# rekick2015-fixed-Prototyp.net
KiCad netlist of a schematic drawn in EAGLE
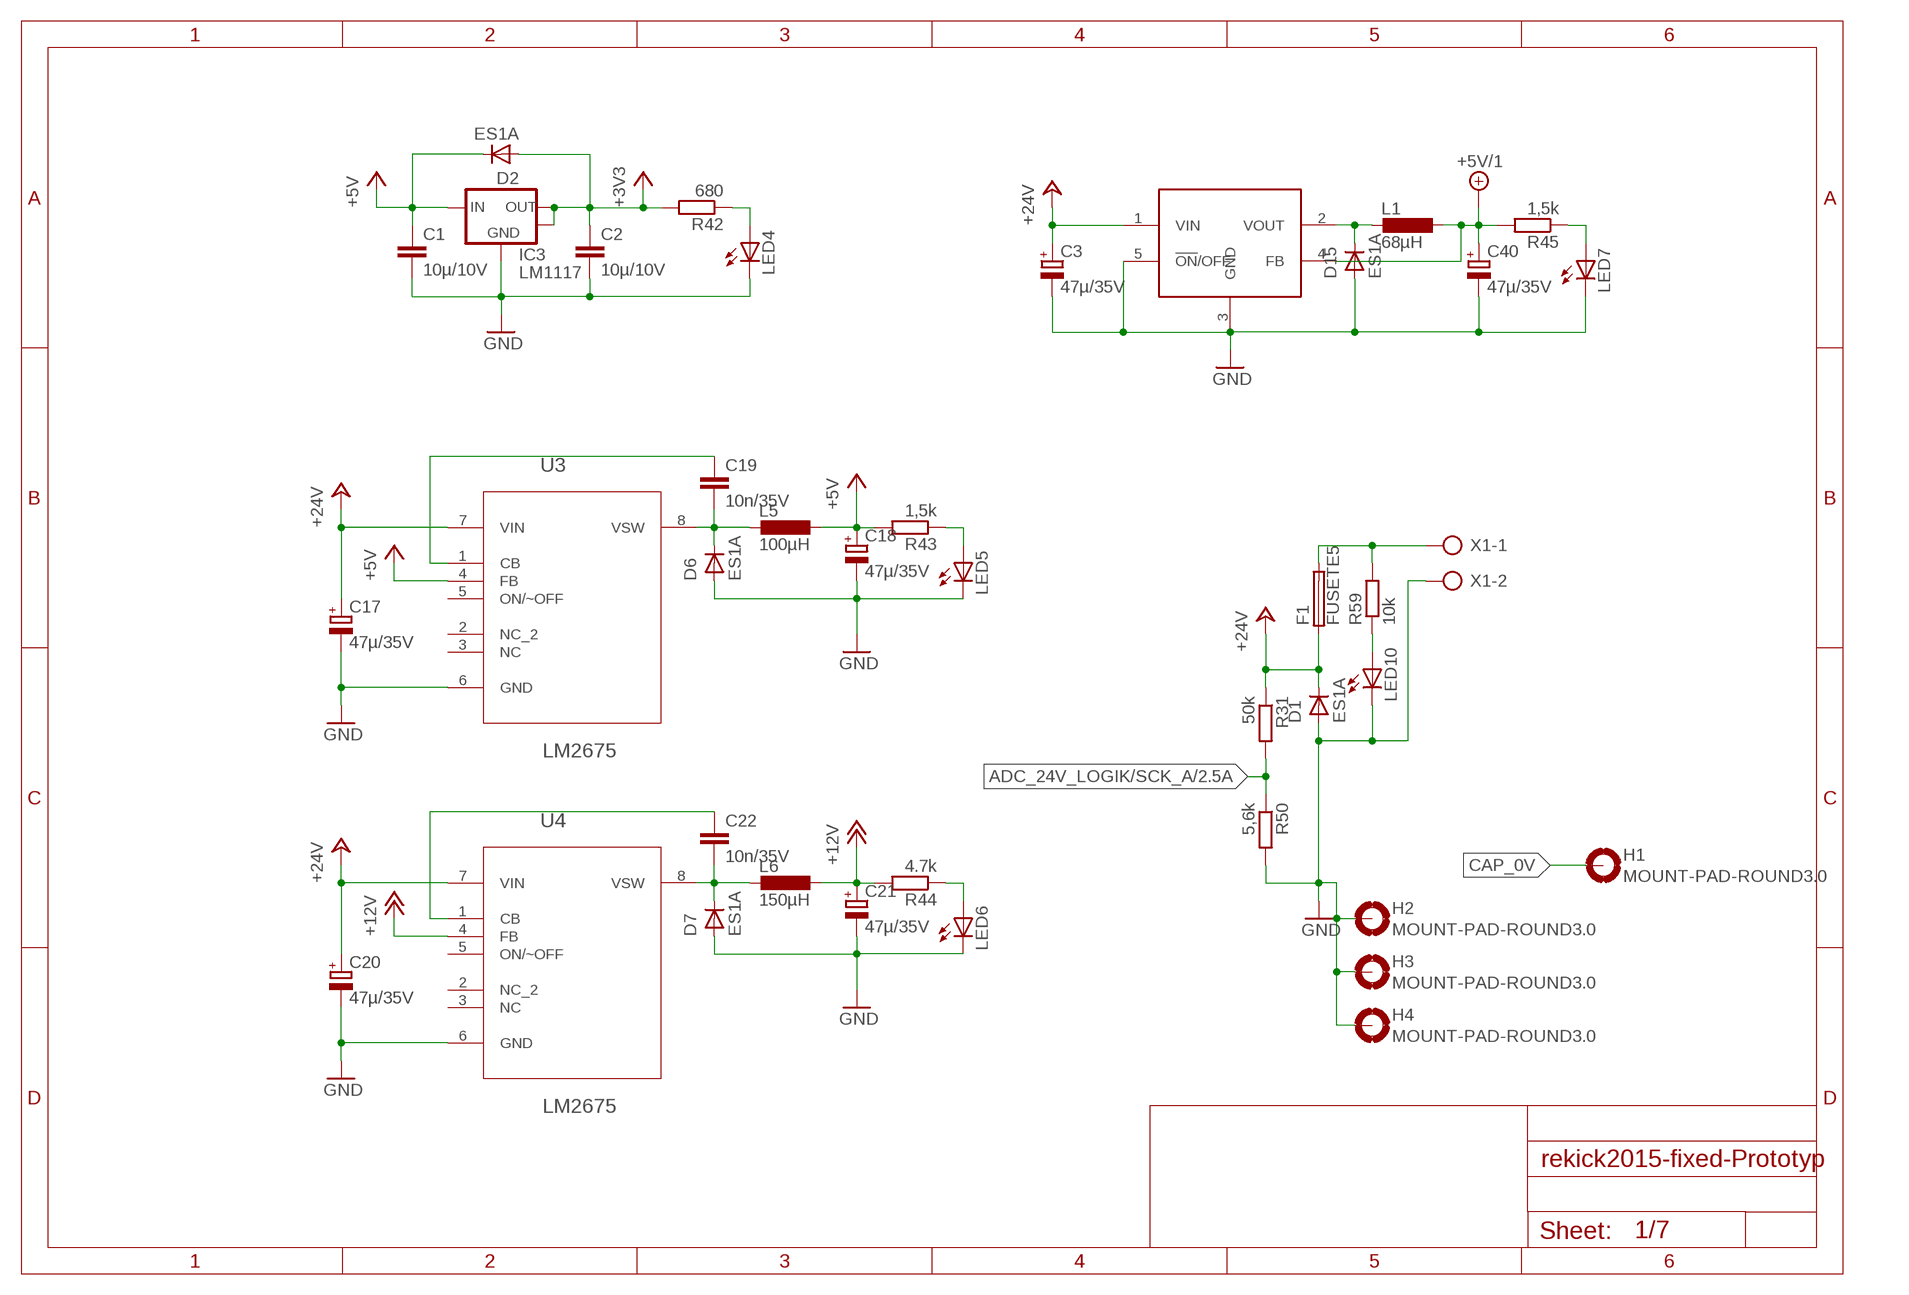
[diagram p0: schematic, sheet 1]
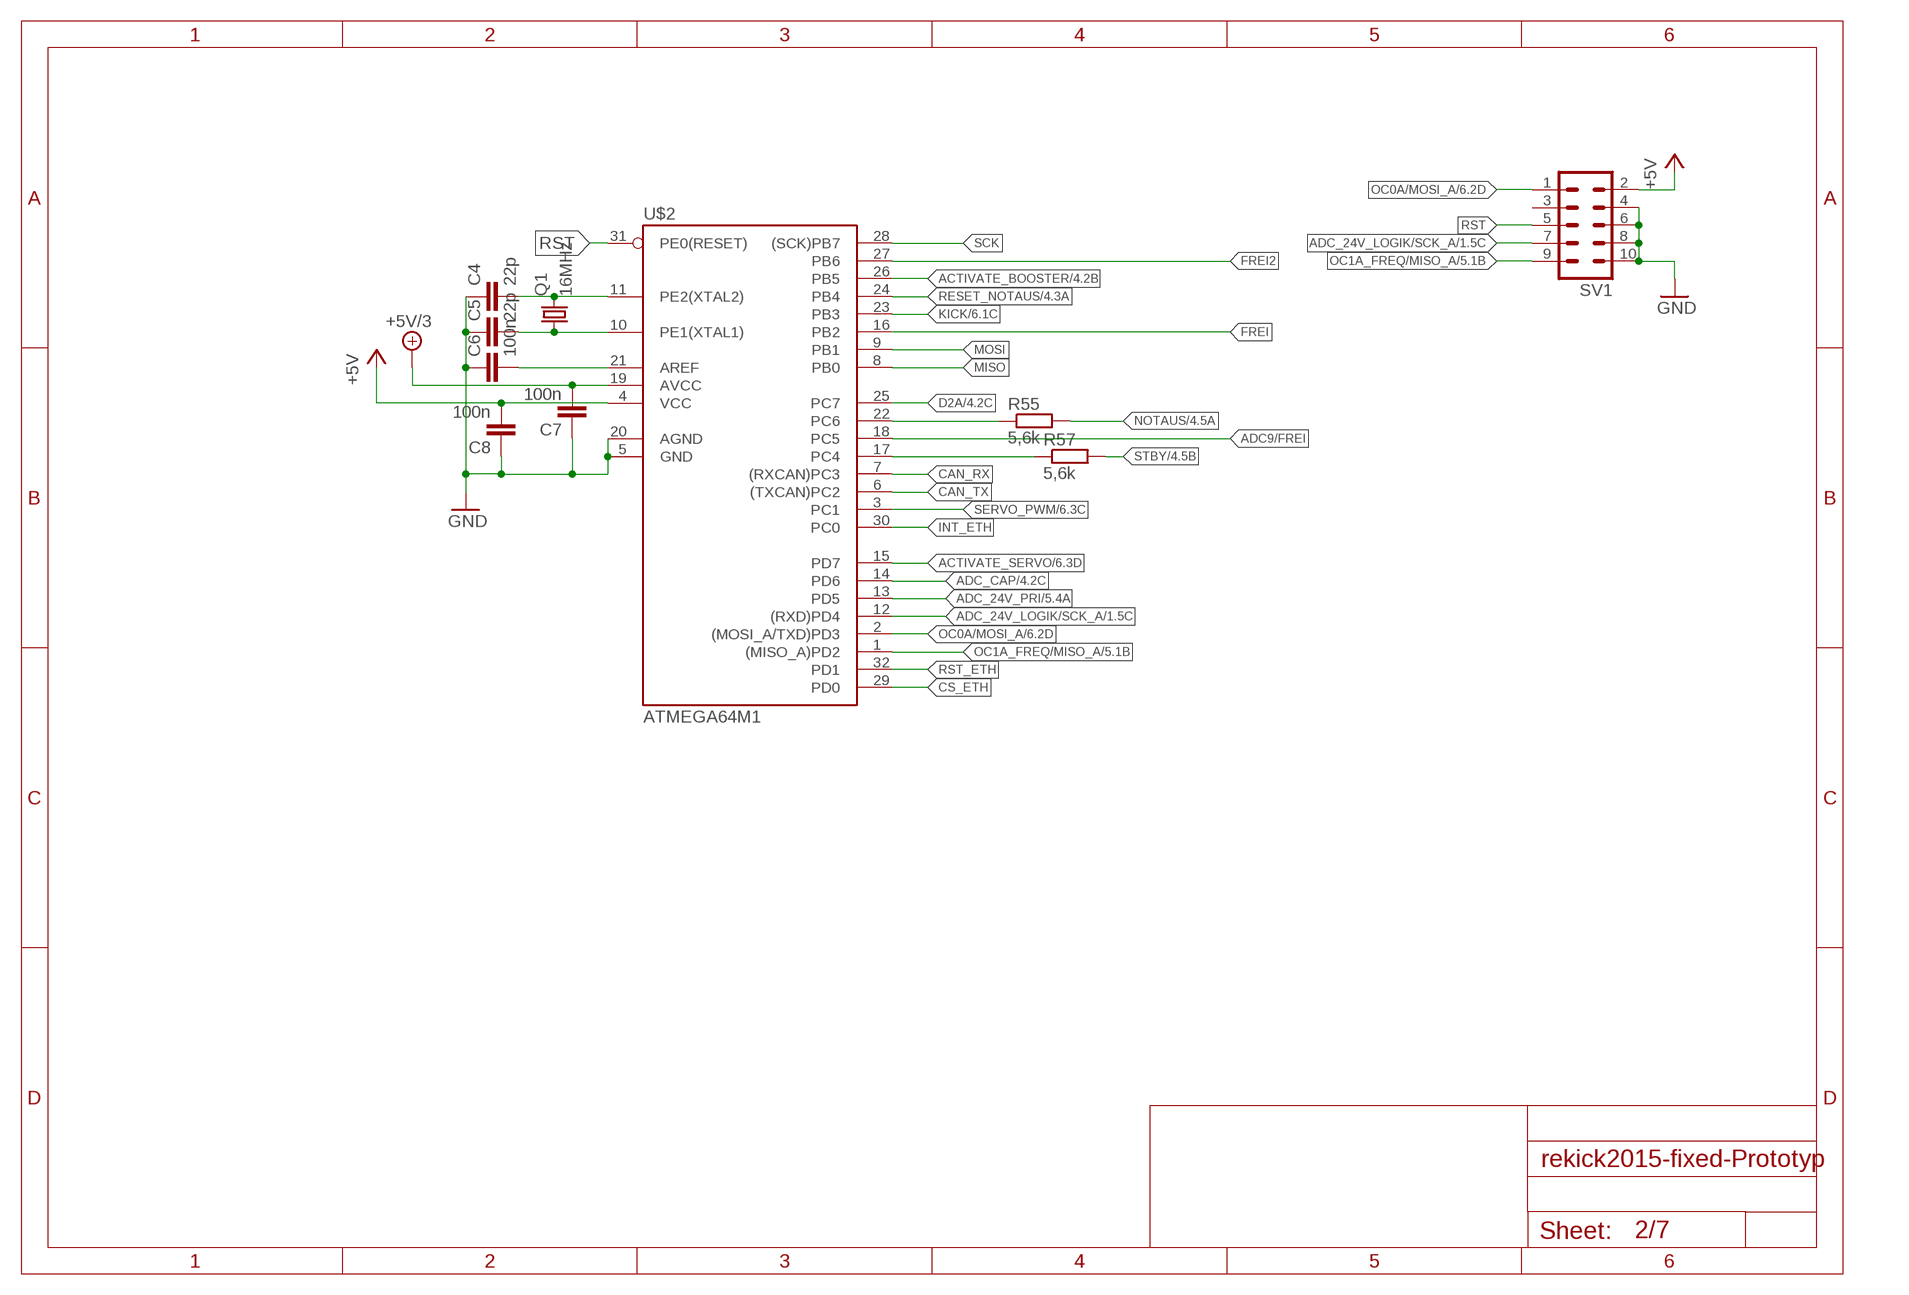
[diagram p1: schematic, sheet 2]
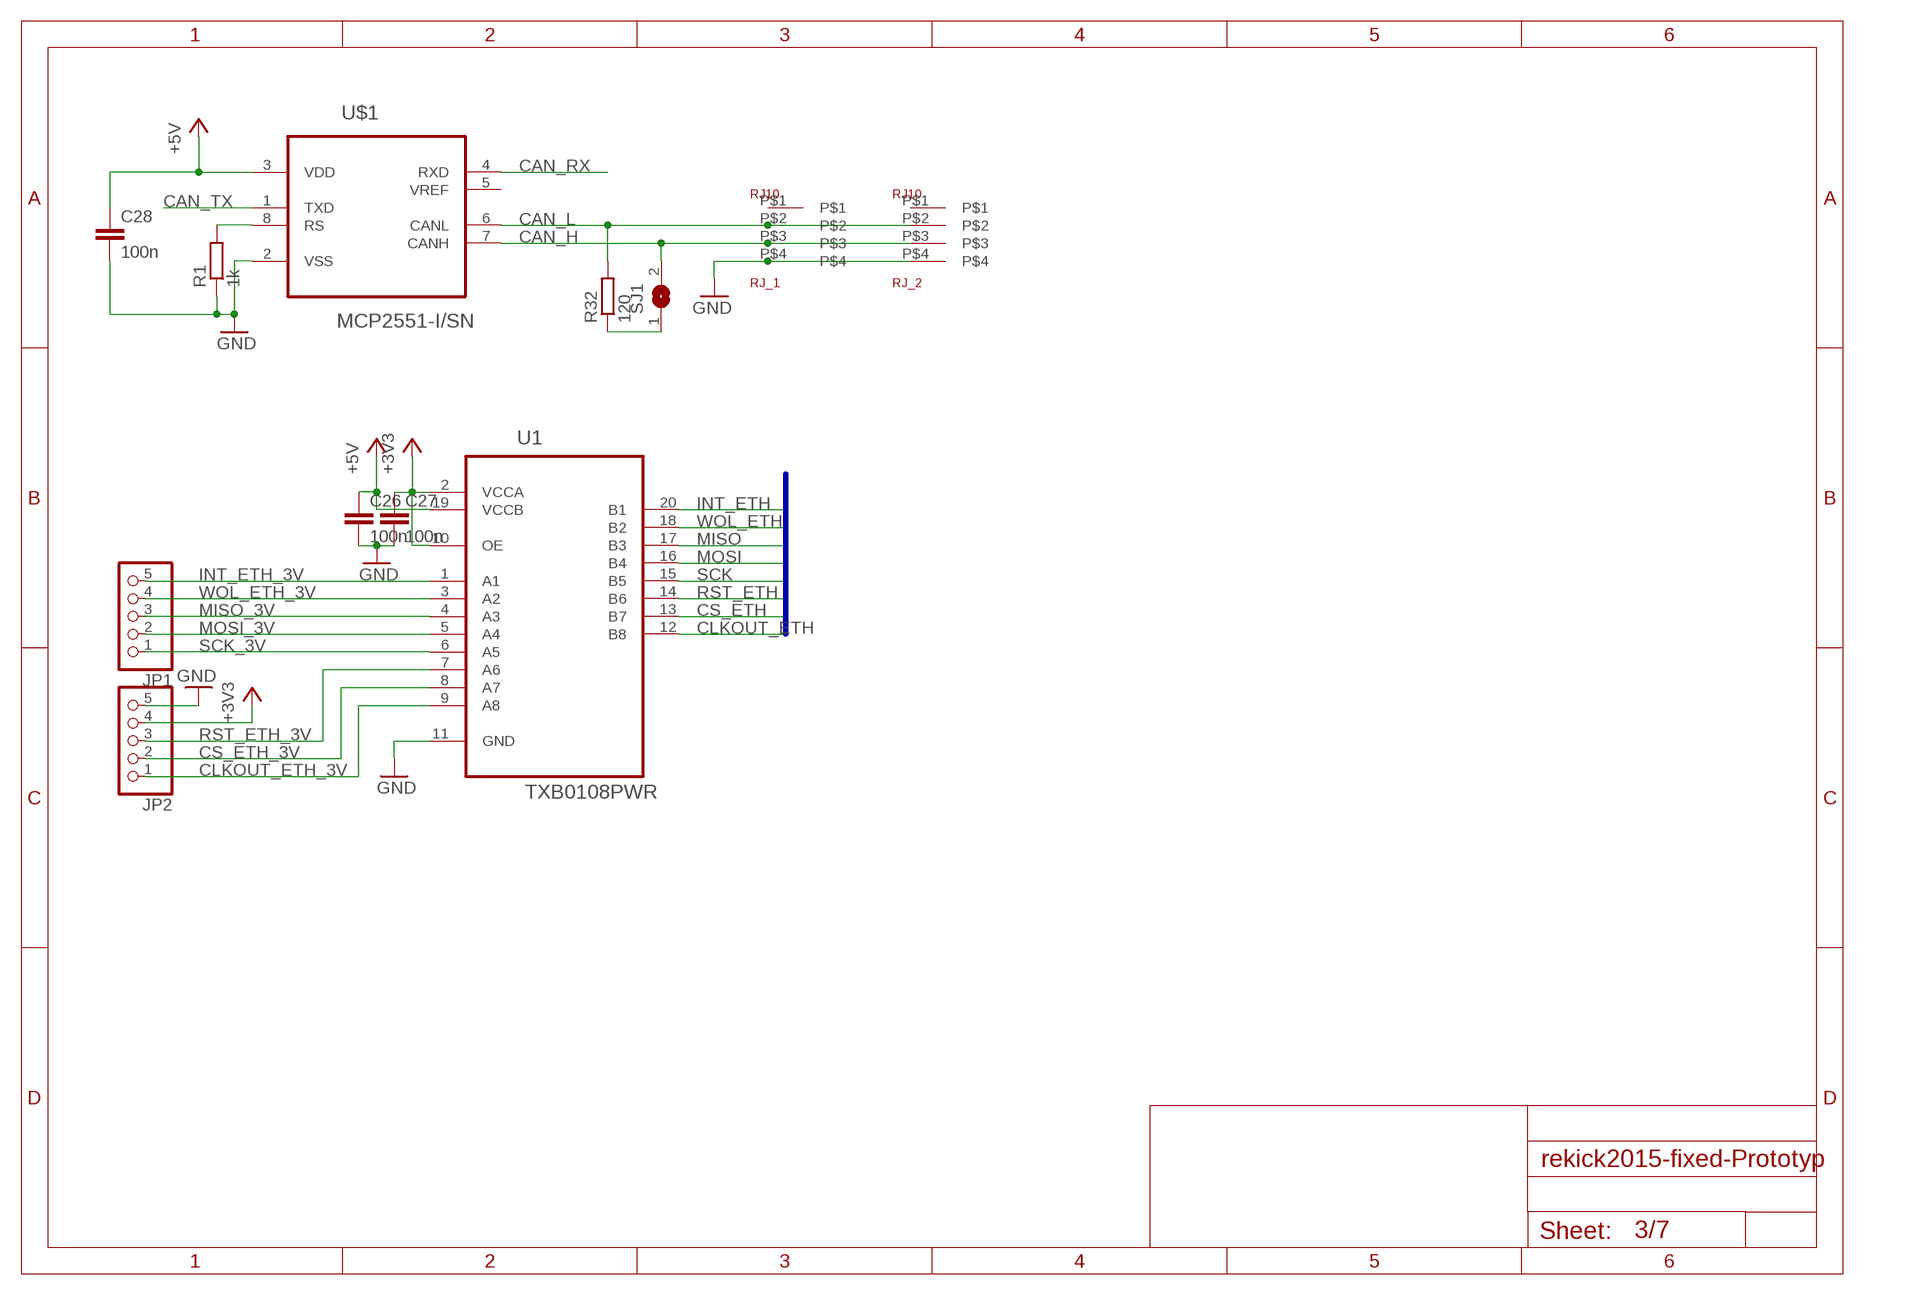
[diagram p2: schematic, sheet 3]
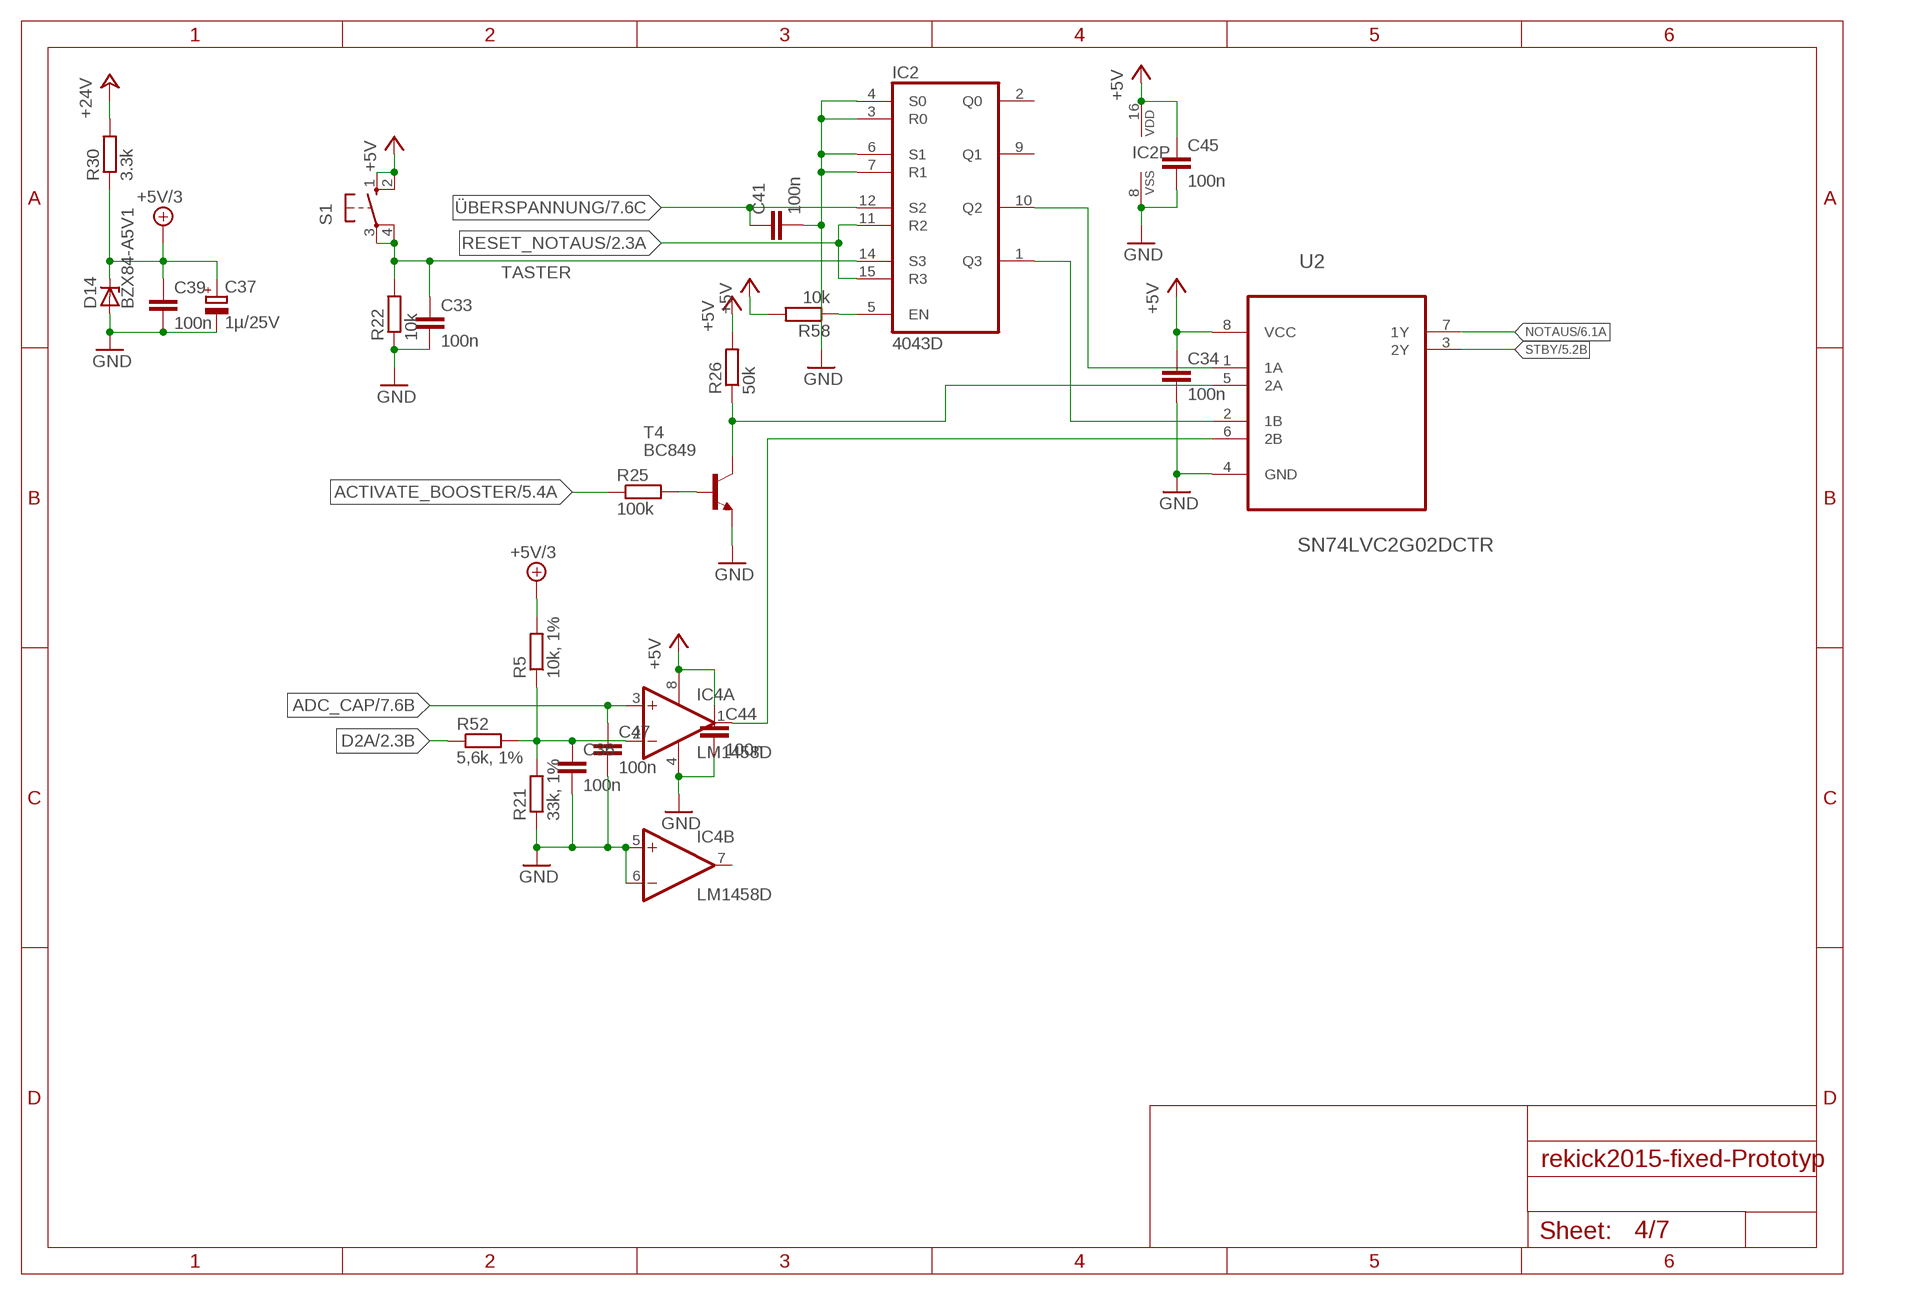
[diagram p3: schematic, sheet 4]
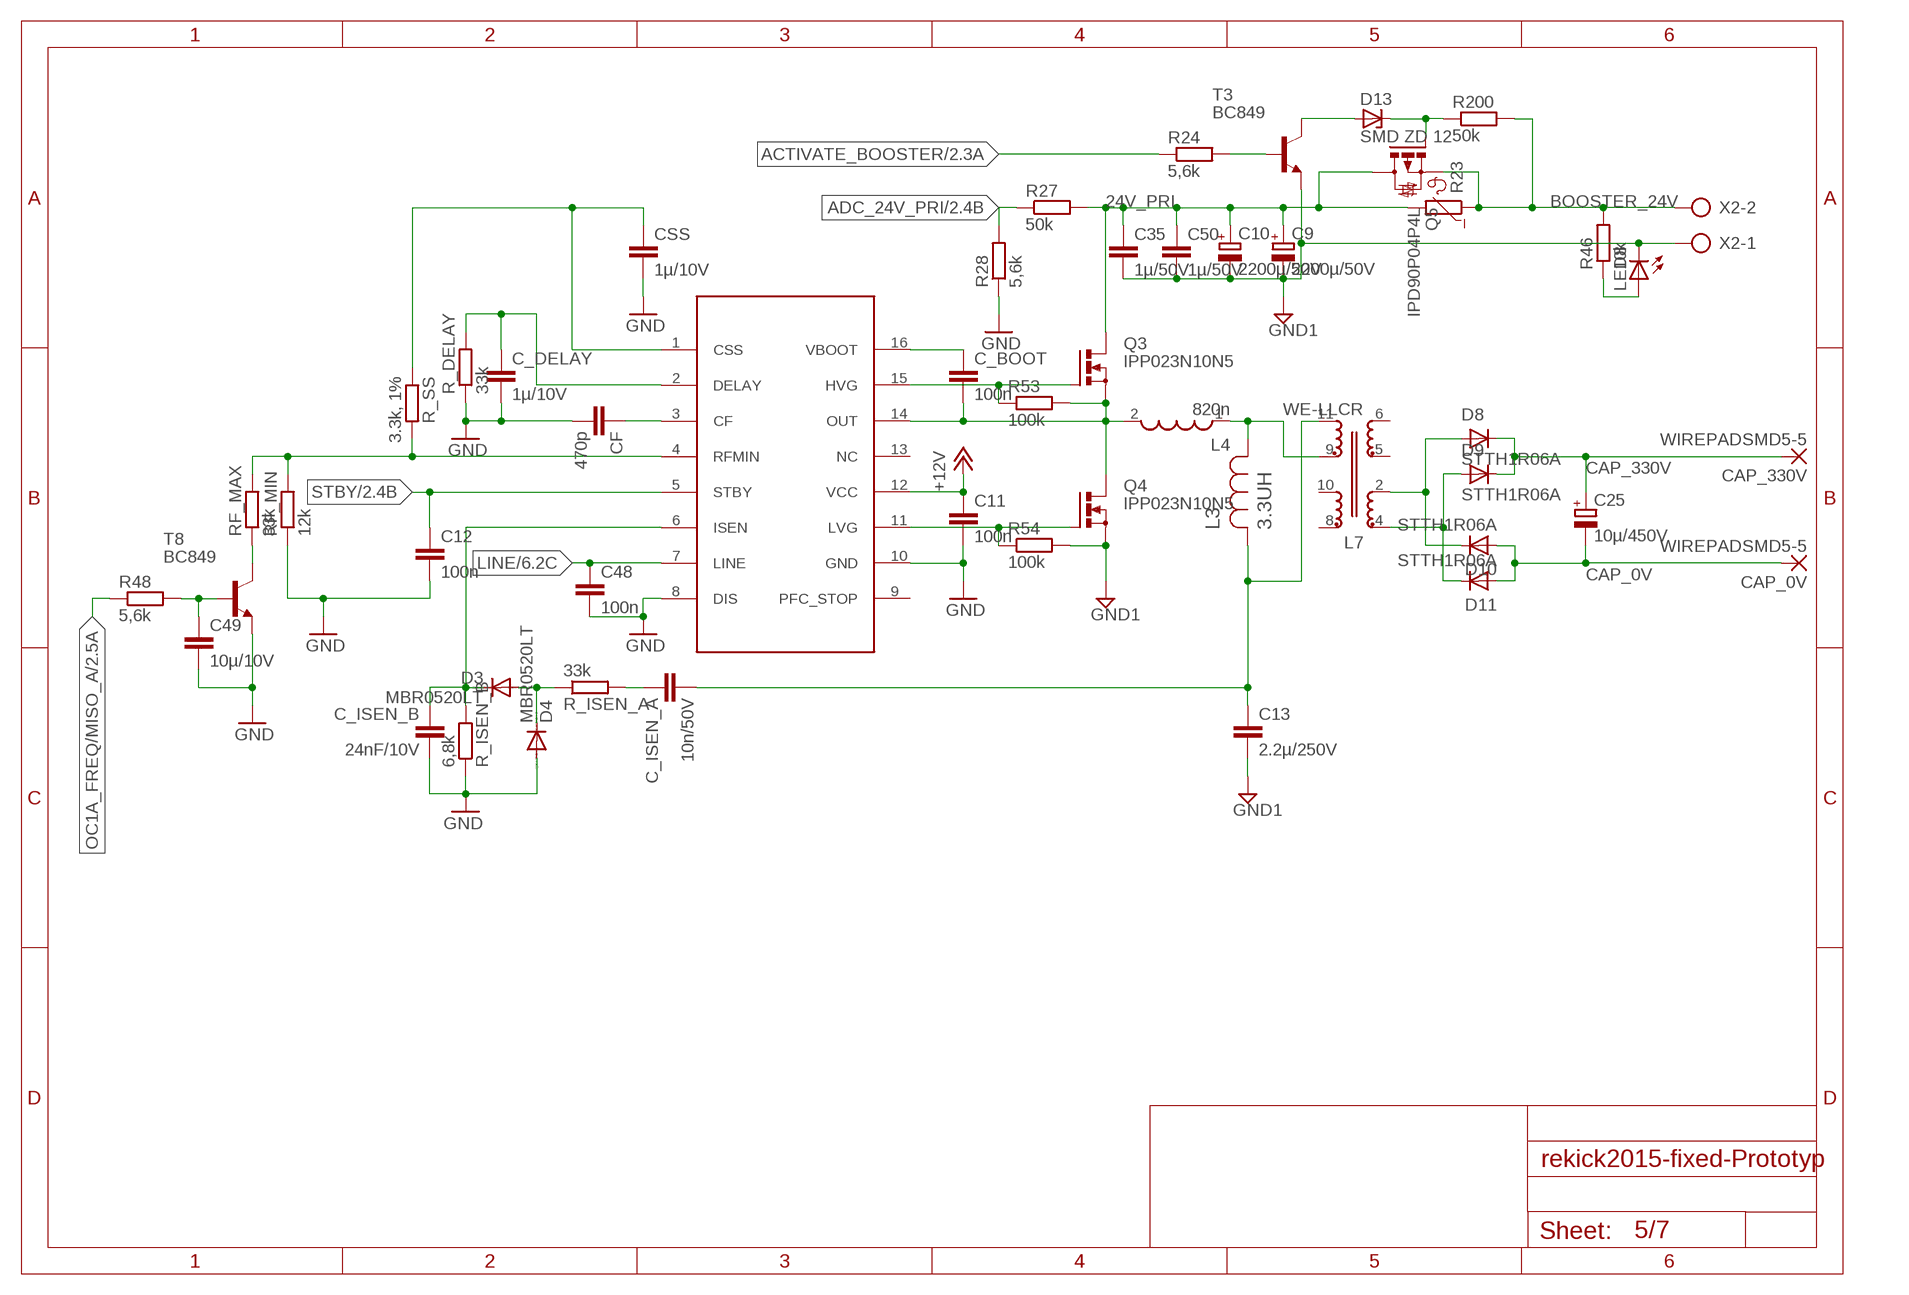
[diagram p4: schematic, sheet 5]
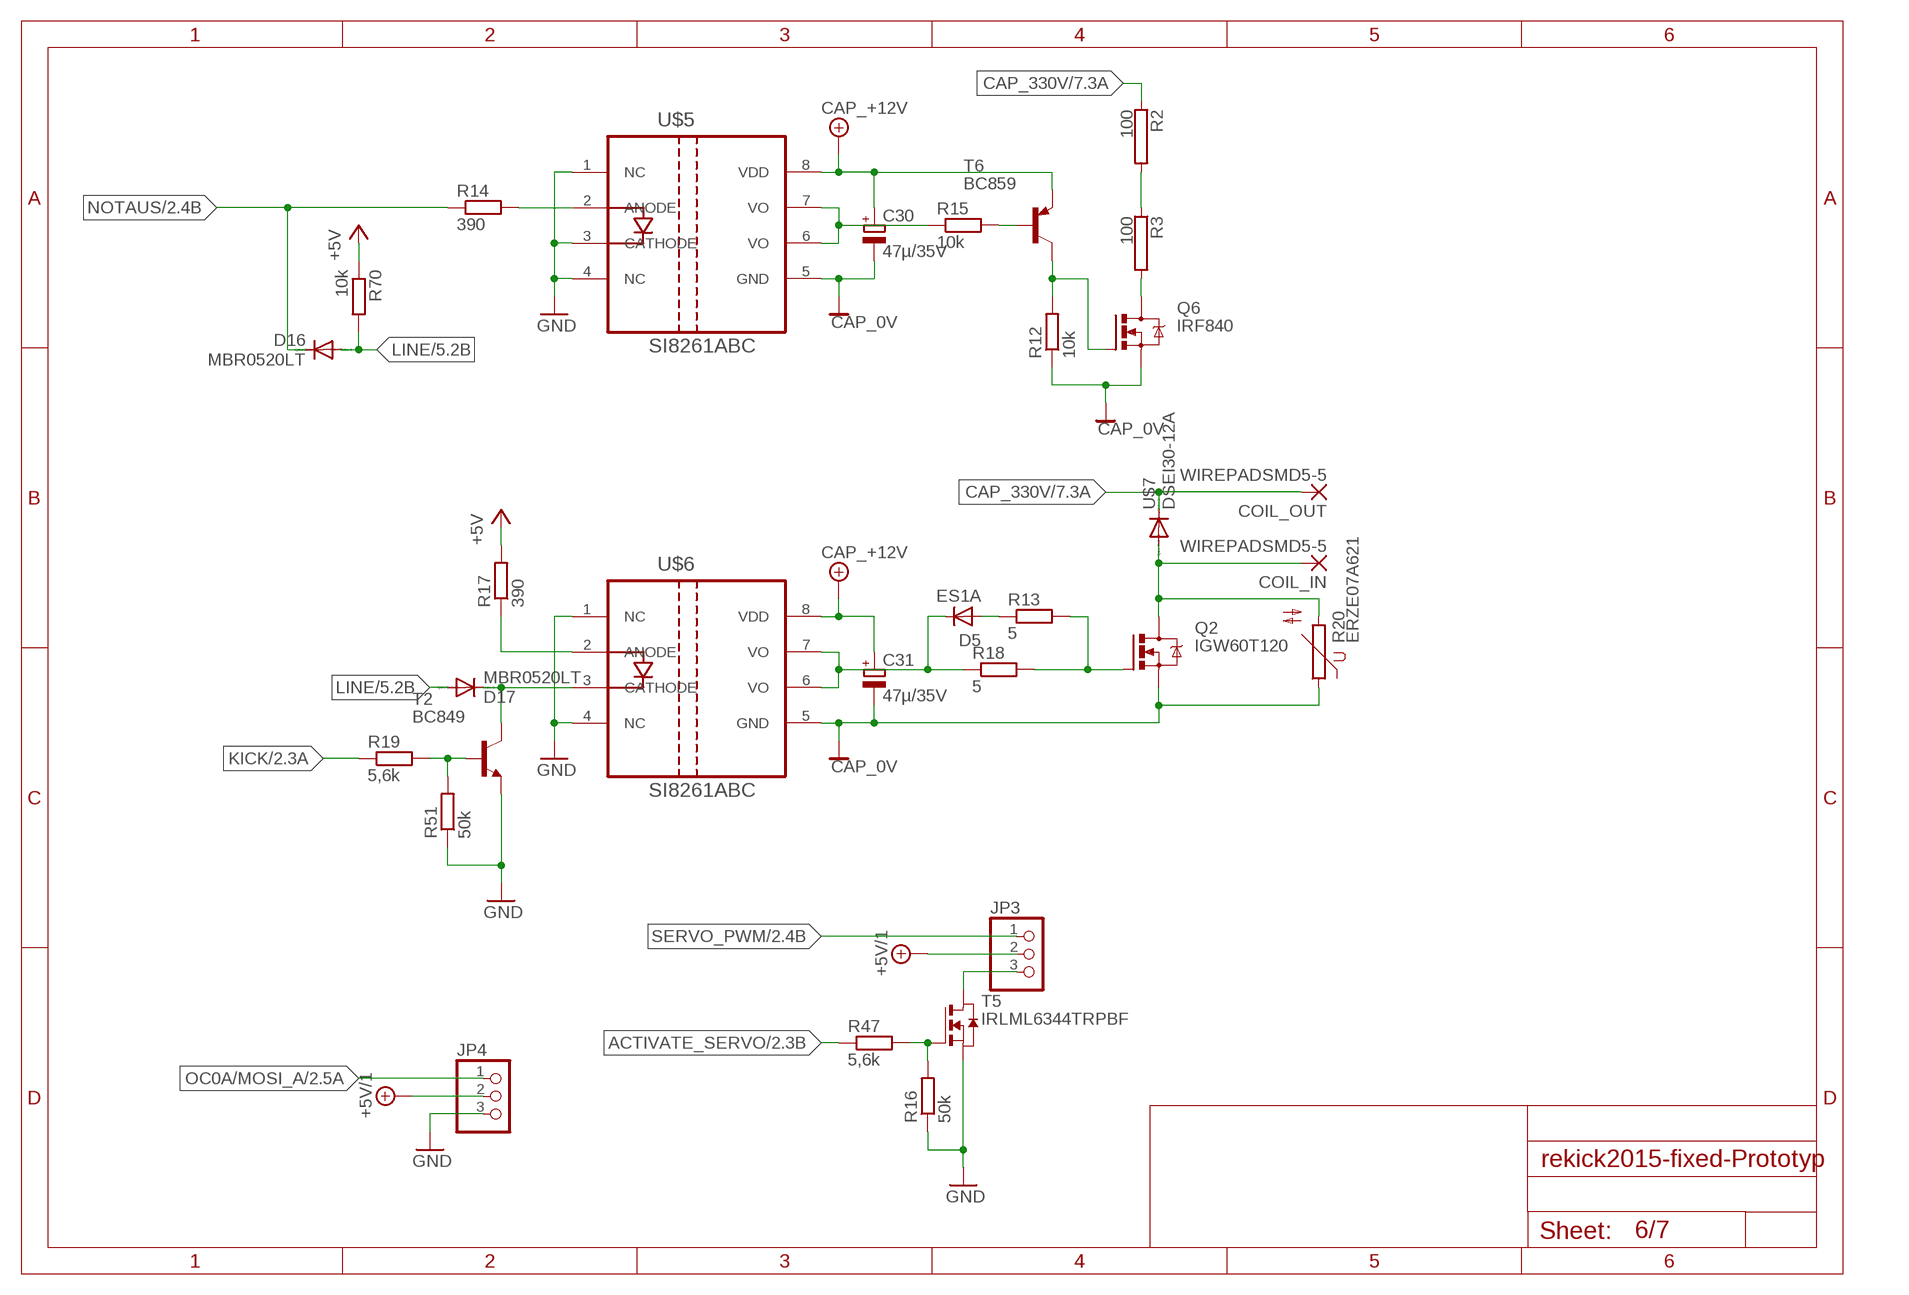
[diagram p5: schematic, sheet 6]
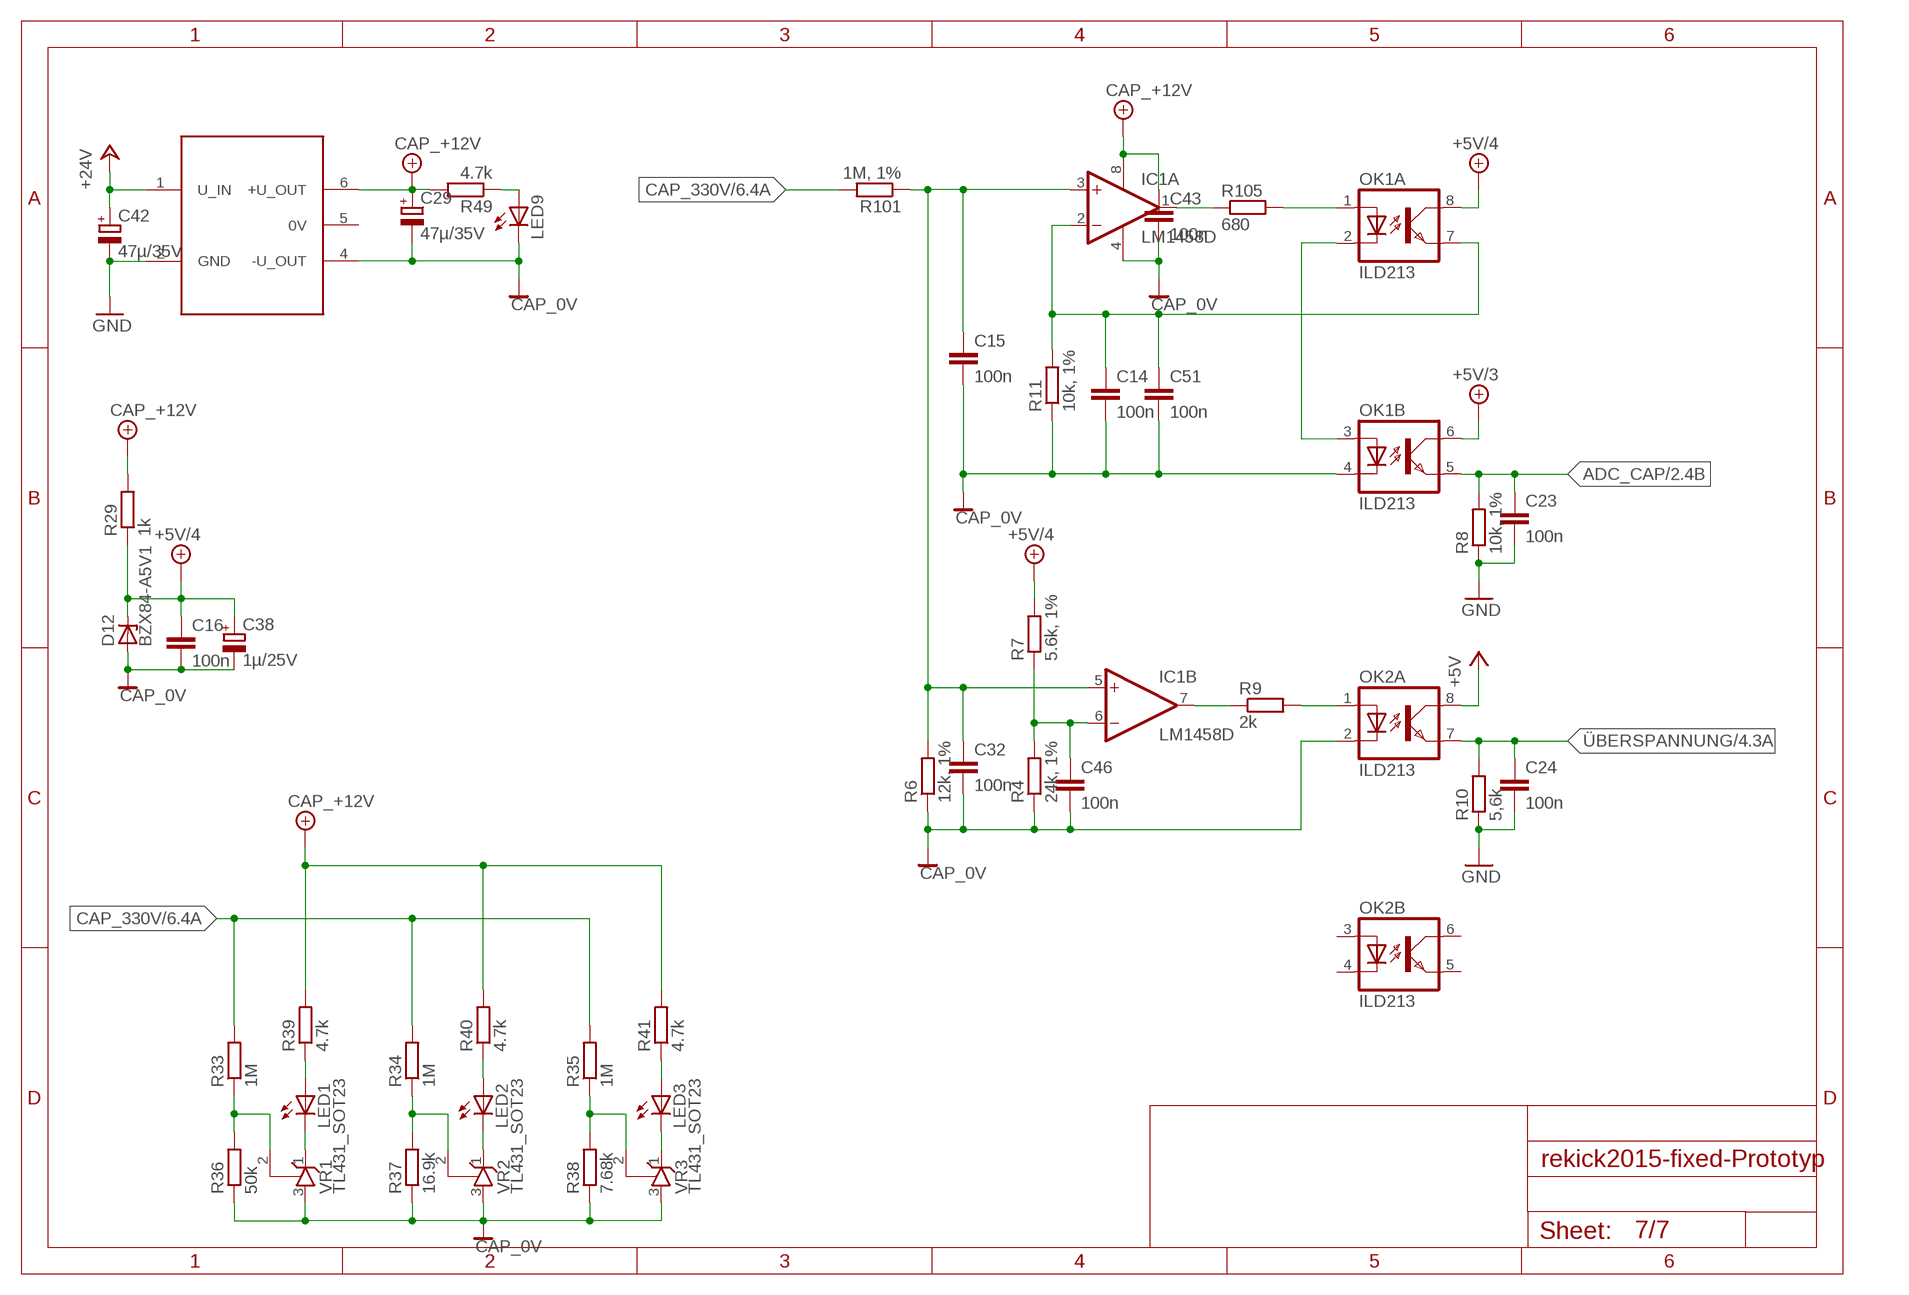
[diagram p6: schematic, sheet 7]

(export (version "E")
  (design (tool "Eeschema 10.0.6"))
  (components
    (comp (ref "C14")
      (value "100n")
      (footprint "eagle-import:C0603")
      (libsource (lib "eagle-import") (part "C-EUC0603"))
    )
    (comp (ref "C15")
      (value "100n")
      (footprint "eagle-import:C0603")
      (libsource (lib "eagle-import") (part "C-EUC0603"))
    )
    (comp (ref "C16")
      (value "100n")
      (footprint "eagle-import:C0603")
      (libsource (lib "eagle-import") (part "C-EUC0603"))
    )
    (comp (ref "C23")
      (value "100n")
      (footprint "eagle-import:C0603")
      (libsource (lib "eagle-import") (part "C-EUC0603"))
    )
    (comp (ref "C24")
      (value "100n")
      (footprint "eagle-import:C0603")
      (libsource (lib "eagle-import") (part "C-EUC0603"))
    )
    (comp (ref "C29")
      (value "47µ/35V")
      (footprint "eagle-import:PANASONIC_D")
      (libsource (lib "eagle-import") (part "CPOL-EUD"))
    )
    (comp (ref "C32")
      (value "100n")
      (footprint "eagle-import:C0603")
      (libsource (lib "eagle-import") (part "C-EUC0603"))
    )
    (comp (ref "C38")
      (value "1µ/25V")
      (footprint "eagle-import:SMC_A")
      (libsource (lib "eagle-import") (part "CPOL-EUSMCA"))
    )
    (comp (ref "C42")
      (value "47µ/35V")
      (footprint "eagle-import:PANASONIC_D")
      (libsource (lib "eagle-import") (part "CPOL-EUD"))
    )
    (comp (ref "C43")
      (value "100n")
      (footprint "eagle-import:C0603")
      (libsource (lib "eagle-import") (part "C-EUC0603"))
    )
    (comp (ref "C46")
      (value "100n")
      (footprint "eagle-import:C0603")
      (libsource (lib "eagle-import") (part "C-EUC0603"))
    )
    (comp (ref "C51")
      (value "100n")
      (footprint "eagle-import:C0603")
      (libsource (lib "eagle-import") (part "C-EUC0603"))
    )
    (comp (ref "D12")
      (value "BZX84-A5V1")
      (footprint "eagle-import:TO236")
      (libsource (lib "eagle-import") (part "BZX84CSMD"))
    )
    (comp (ref "IC1")
      (value "LM1458D")
      (footprint "eagle-import:SO08")
      (libsource (lib "eagle-import") (part "1458DLM"))
    )
    (comp (ref "LED1")
      (value "LEDCHIP-LED0805")
      (footprint "eagle-import:CHIP-LED0805")
      (libsource (lib "eagle-import") (part "LEDCHIP-LED0805"))
    )
    (comp (ref "LED2")
      (value "LEDCHIP-LED0805")
      (footprint "eagle-import:CHIP-LED0805")
      (libsource (lib "eagle-import") (part "LEDCHIP-LED0805"))
    )
    (comp (ref "LED3")
      (value "LEDCHIP-LED0805")
      (footprint "eagle-import:CHIP-LED0805")
      (libsource (lib "eagle-import") (part "LEDCHIP-LED0805"))
    )
    (comp (ref "LED9")
      (value "LEDCHIP-LED0805")
      (footprint "eagle-import:CHIP-LED0805")
      (libsource (lib "eagle-import") (part "LEDCHIP-LED0805"))
    )
    (comp (ref "OK1")
      (value "ILD213")
      (footprint "eagle-import:SOIC08")
      (libsource (lib "eagle-import") (part "ILD213"))
    )
    (comp (ref "OK2")
      (value "ILD213")
      (footprint "eagle-import:SOIC08")
      (libsource (lib "eagle-import") (part "ILD213"))
    )
    (comp (ref "R4")
      (value "24k, 1%")
      (footprint "eagle-import:R0805")
      (libsource (lib "eagle-import") (part "R-EU_R0805"))
    )
    (comp (ref "R6")
      (value "12k, 1%")
      (footprint "eagle-import:R0805")
      (libsource (lib "eagle-import") (part "R-EU_R0805"))
    )
    (comp (ref "R7")
      (value "5.6k, 1%")
      (footprint "eagle-import:R0805")
      (libsource (lib "eagle-import") (part "R-EU_R0805"))
    )
    (comp (ref "R8")
      (value "10k, 1%")
      (footprint "eagle-import:R0805")
      (libsource (lib "eagle-import") (part "R-EU_R0805"))
    )
    (comp (ref "R9")
      (value "2k")
      (footprint "eagle-import:R0805")
      (libsource (lib "eagle-import") (part "R-EU_R0805"))
    )
    (comp (ref "R10")
      (value "5,6k")
      (footprint "eagle-import:R0805")
      (libsource (lib "eagle-import") (part "R-EU_R0805"))
    )
    (comp (ref "R11")
      (value "10k, 1%")
      (footprint "eagle-import:R0805")
      (libsource (lib "eagle-import") (part "R-EU_R0805"))
    )
    (comp (ref "R29")
      (value "1k")
      (footprint "eagle-import:R0805")
      (libsource (lib "eagle-import") (part "R-EU_R0805"))
    )
    (comp (ref "R33")
      (value "1M")
      (footprint "eagle-import:R2512")
      (libsource (lib "eagle-import") (part "R-EU_R2512"))
    )
    (comp (ref "R34")
      (value "1M")
      (footprint "eagle-import:R2512")
      (libsource (lib "eagle-import") (part "R-EU_R2512"))
    )
    (comp (ref "R35")
      (value "1M")
      (footprint "eagle-import:R2512")
      (libsource (lib "eagle-import") (part "R-EU_R2512"))
    )
    (comp (ref "R36")
      (value "50k")
      (footprint "eagle-import:R0805")
      (libsource (lib "eagle-import") (part "R-EU_R0805"))
    )
    (comp (ref "R37")
      (value "16.9k")
      (footprint "eagle-import:R0805")
      (libsource (lib "eagle-import") (part "R-EU_R0805"))
    )
    (comp (ref "R38")
      (value "7.68k")
      (footprint "eagle-import:R0805")
      (libsource (lib "eagle-import") (part "R-EU_R0805"))
    )
    (comp (ref "R39")
      (value "4.7k")
      (footprint "eagle-import:R0805")
      (libsource (lib "eagle-import") (part "R-EU_R0805"))
    )
    (comp (ref "R40")
      (value "4.7k")
      (footprint "eagle-import:R0805")
      (libsource (lib "eagle-import") (part "R-EU_R0805"))
    )
    (comp (ref "R41")
      (value "4.7k")
      (footprint "eagle-import:R0805")
      (libsource (lib "eagle-import") (part "R-EU_R0805"))
    )
    (comp (ref "R49")
      (value "4.7k")
      (footprint "eagle-import:R0805")
      (libsource (lib "eagle-import") (part "R-EU_R0805"))
    )
    (comp (ref "R101")
      (value "1M, 1%")
      (footprint "eagle-import:R2512")
      (libsource (lib "eagle-import") (part "R-EU_R2512"))
    )
    (comp (ref "R105")
      (value "680")
      (footprint "eagle-import:R0805")
      (libsource (lib "eagle-import") (part "R-EU_R0805"))
    )
    (comp (ref "U$4")
      (value "TMH-D")
      (footprint "eagle-import:TMH-D")
      (libsource (lib "eagle-import") (part "TMH-D"))
    )
    (comp (ref "VR1")
      (value "TL431_SOT23")
      (footprint "eagle-import:SOT23")
      (libsource (lib "eagle-import") (part "TL431_SOT23"))
    )
    (comp (ref "VR2")
      (value "TL431_SOT23")
      (footprint "eagle-import:SOT23")
      (libsource (lib "eagle-import") (part "TL431_SOT23"))
    )
    (comp (ref "VR3")
      (value "TL431_SOT23")
      (footprint "eagle-import:SOT23")
      (libsource (lib "eagle-import") (part "TL431_SOT23"))
    )
    (comp (ref "C4")
      (value "22p")
      (footprint "eagle-import:C0603")
      (libsource (lib "eagle-import") (part "C-EUC0603"))
    )
    (comp (ref "C5")
      (value "22p")
      (footprint "eagle-import:C0603")
      (libsource (lib "eagle-import") (part "C-EUC0603"))
    )
    (comp (ref "C6")
      (value "100n")
      (footprint "eagle-import:C0603")
      (libsource (lib "eagle-import") (part "C-EUC0603"))
    )
    (comp (ref "C7")
      (value "100n")
      (footprint "eagle-import:C0603")
      (libsource (lib "eagle-import") (part "C-EUC0603"))
    )
    (comp (ref "C8")
      (value "100n")
      (footprint "eagle-import:C0603")
      (libsource (lib "eagle-import") (part "C-EUC0603"))
    )
    (comp (ref "Q1")
      (value "16MHz")
      (footprint "eagle-import:HC49UP")
      (libsource (lib "eagle-import") (part "CRYSTALHC49UP"))
    )
    (comp (ref "R55")
      (value "5,6k")
      (footprint "eagle-import:R0805")
      (libsource (lib "eagle-import") (part "R-EU_R0805"))
    )
    (comp (ref "R57")
      (value "5,6k")
      (footprint "eagle-import:R0805")
      (libsource (lib "eagle-import") (part "R-EU_R0805"))
    )
    (comp (ref "SV1")
      (value "ML10")
      (footprint "eagle-import:ML10")
      (libsource (lib "eagle-import") (part "ML10"))
    )
    (comp (ref "U$2")
      (value "ATMEGA64M1")
      (footprint "eagle-import:TQFP32-08")
      (libsource (lib "eagle-import") (part "ATMEGA64M1"))
    )
    (comp (ref "C30")
      (value "47µ/35V")
      (footprint "eagle-import:E2-5")
      (libsource (lib "eagle-import") (part "CPOL-EUE2-5"))
    )
    (comp (ref "C31")
      (value "47µ/35V")
      (footprint "eagle-import:E2-5")
      (libsource (lib "eagle-import") (part "CPOL-EUE2-5"))
    )
    (comp (ref "COIL_IN")
      (value "WIREPADSMD5-5")
      (footprint "eagle-import:5-5")
      (libsource (lib "eagle-import") (part "WIREPADSMD5-5"))
    )
    (comp (ref "COIL_OUT")
      (value "WIREPADSMD5-5")
      (footprint "eagle-import:5-5")
      (libsource (lib "eagle-import") (part "WIREPADSMD5-5"))
    )
    (comp (ref "D5")
      (value "ES1A")
      (footprint "eagle-import:SMA-DO214AC")
      (libsource (lib "eagle-import") (part "GF1"))
    )
    (comp (ref "D16")
      (value "MBR0520LT")
      (footprint "eagle-import:SOD123")
      (libsource (lib "eagle-import") (part "MBR0520LT"))
    )
    (comp (ref "D17")
      (value "MBR0520LT")
      (footprint "eagle-import:SOD123")
      (libsource (lib "eagle-import") (part "MBR0520LT"))
    )
    (comp (ref "JP3")
      (value "PINHD-1X3")
      (footprint "eagle-import:1X03")
      (libsource (lib "eagle-import") (part "PINHD-1X3"))
    )
    (comp (ref "JP4")
      (value "PINHD-1X3")
      (footprint "eagle-import:1X03")
      (libsource (lib "eagle-import") (part "PINHD-1X3"))
    )
    (comp (ref "Q2")
      (value "IGW60T120")
      (footprint "eagle-import:TO247BV")
      (libsource (lib "eagle-import") (part "IRFPC40"))
    )
    (comp (ref "Q6")
      (value "IRF840")
      (footprint "eagle-import:TO220BV")
      (libsource (lib "eagle-import") (part "IRF740"))
    )
    (comp (ref "R2")
      (value "100")
      (footprint "eagle-import:HS25")
      (libsource (lib "eagle-import") (part "RHS25"))
    )
    (comp (ref "R3")
      (value "100")
      (footprint "eagle-import:HS25")
      (libsource (lib "eagle-import") (part "RHS25"))
    )
    (comp (ref "R12")
      (value "10k")
      (footprint "eagle-import:R0805")
      (libsource (lib "eagle-import") (part "R-EU_R0805"))
    )
    (comp (ref "R13")
      (value "5")
      (footprint "eagle-import:R2512")
      (libsource (lib "eagle-import") (part "R-EU_R2512"))
    )
    (comp (ref "R14")
      (value "390")
      (footprint "eagle-import:R0805")
      (libsource (lib "eagle-import") (part "R-EU_R0805"))
    )
    (comp (ref "R15")
      (value "10k")
      (footprint "eagle-import:R0805")
      (libsource (lib "eagle-import") (part "R-EU_R0805"))
    )
    (comp (ref "R16")
      (value "50k")
      (footprint "eagle-import:R0805")
      (libsource (lib "eagle-import") (part "R-EU_R0805"))
    )
    (comp (ref "R17")
      (value "390")
      (footprint "eagle-import:R0805")
      (libsource (lib "eagle-import") (part "R-EU_R0805"))
    )
    (comp (ref "R18")
      (value "5")
      (footprint "eagle-import:R2512")
      (libsource (lib "eagle-import") (part "R-EU_R2512"))
    )
    (comp (ref "R19")
      (value "5,6k")
      (footprint "eagle-import:R0805")
      (libsource (lib "eagle-import") (part "R-EU_R0805"))
    )
    (comp (ref "R20")
      (value "ERZE07A621")
      (footprint "eagle-import:S10K385")
      (libsource (lib "eagle-import") (part "S10K385"))
    )
    (comp (ref "R47")
      (value "5,6k")
      (footprint "eagle-import:R0805")
      (libsource (lib "eagle-import") (part "R-EU_R0805"))
    )
    (comp (ref "R51")
      (value "50k")
      (footprint "eagle-import:R0805")
      (libsource (lib "eagle-import") (part "R-EU_R0805"))
    )
    (comp (ref "R70")
      (value "10k")
      (footprint "eagle-import:R0805")
      (libsource (lib "eagle-import") (part "R-EU_R0805"))
    )
    (comp (ref "T2")
      (value "BC849")
      (footprint "eagle-import:SOT23")
      (libsource (lib "eagle-import") (part "BC849"))
    )
    (comp (ref "T5")
      (value "IRLML6344TRPBF")
      (footprint "eagle-import:SOT-23")
      (libsource (lib "eagle-import") (part "NMOSSOT23"))
    )
    (comp (ref "T6")
      (value "BC859")
      (footprint "eagle-import:SOT23-BEC")
      (libsource (lib "eagle-import") (part "-PNP-SOT23-BECBC858C"))
    )
    (comp (ref "U$5")
      (value "SI8261ABC")
      (footprint "eagle-import:SOIC-8")
      (libsource (lib "eagle-import") (part "SI8261ABC"))
    )
    (comp (ref "U$6")
      (value "SI8261ABC")
      (footprint "eagle-import:SOIC-8")
      (libsource (lib "eagle-import") (part "SI8261ABC"))
    )
    (comp (ref "U$7")
      (value "DSEI30-12A")
      (footprint "eagle-import:TO247AD")
      (libsource (lib "eagle-import") (part "DSEI30-12A"))
    )
    (comp (ref "C1")
      (value "10µ/10V")
      (footprint "eagle-import:C0603")
      (libsource (lib "eagle-import") (part "C-EUC0603"))
    )
    (comp (ref "C2")
      (value "10µ/10V")
      (footprint "eagle-import:C0603")
      (libsource (lib "eagle-import") (part "C-EUC0603"))
    )
    (comp (ref "C3")
      (value "47µ/35V")
      (footprint "eagle-import:PANASONIC_D")
      (libsource (lib "eagle-import") (part "CPOL-EUD"))
    )
    (comp (ref "C17")
      (value "47µ/35V")
      (footprint "eagle-import:PANASONIC_D")
      (libsource (lib "eagle-import") (part "CPOL-EUD"))
    )
    (comp (ref "C18")
      (value "47µ/35V")
      (footprint "eagle-import:PANASONIC_D")
      (libsource (lib "eagle-import") (part "CPOL-EUD"))
    )
    (comp (ref "C19")
      (value "10n/35V")
      (footprint "eagle-import:C0603")
      (libsource (lib "eagle-import") (part "C-EUC0603"))
    )
    (comp (ref "C20")
      (value "47µ/35V")
      (footprint "eagle-import:PANASONIC_D")
      (libsource (lib "eagle-import") (part "CPOL-EUD"))
    )
    (comp (ref "C21")
      (value "47µ/35V")
      (footprint "eagle-import:PANASONIC_D")
      (libsource (lib "eagle-import") (part "CPOL-EUD"))
    )
    (comp (ref "C22")
      (value "10n/35V")
      (footprint "eagle-import:C0603")
      (libsource (lib "eagle-import") (part "C-EUC0603"))
    )
    (comp (ref "C40")
      (value "47µ/35V")
      (footprint "eagle-import:PANASONIC_D")
      (libsource (lib "eagle-import") (part "CPOL-EUD"))
    )
    (comp (ref "D1")
      (value "ES1A")
      (footprint "eagle-import:SMA-DO214AC")
      (libsource (lib "eagle-import") (part "GF1"))
    )
    (comp (ref "D2")
      (value "ES1A")
      (footprint "eagle-import:SMA-DO214AC")
      (libsource (lib "eagle-import") (part "GF1"))
    )
    (comp (ref "D6")
      (value "ES1A")
      (footprint "eagle-import:SMA-DO214AC")
      (libsource (lib "eagle-import") (part "GF1"))
    )
    (comp (ref "D7")
      (value "ES1A")
      (footprint "eagle-import:SMA-DO214AC")
      (libsource (lib "eagle-import") (part "GF1"))
    )
    (comp (ref "D15")
      (value "ES1A")
      (footprint "eagle-import:SMA-DO214AC")
      (libsource (lib "eagle-import") (part "GF1"))
    )
    (comp (ref "F1")
      (value "FUSETE5")
      (footprint "eagle-import:TE5")
      (libsource (lib "eagle-import") (part "FUSETE5"))
    )
    (comp (ref "H1")
      (value "MOUNT-PAD-ROUND3.0")
      (footprint "eagle-import:3,0-PAD")
      (libsource (lib "eagle-import") (part "MOUNT-PAD-ROUND3.0"))
    )
    (comp (ref "H2")
      (value "MOUNT-PAD-ROUND3.0")
      (footprint "eagle-import:3,0-PAD")
      (libsource (lib "eagle-import") (part "MOUNT-PAD-ROUND3.0"))
    )
    (comp (ref "H3")
      (value "MOUNT-PAD-ROUND3.0")
      (footprint "eagle-import:3,0-PAD")
      (libsource (lib "eagle-import") (part "MOUNT-PAD-ROUND3.0"))
    )
    (comp (ref "H4")
      (value "MOUNT-PAD-ROUND3.0")
      (footprint "eagle-import:3,0-PAD")
      (libsource (lib "eagle-import") (part "MOUNT-PAD-ROUND3.0"))
    )
    (comp (ref "IC3")
      (value "LM1117")
      (footprint "eagle-import:SOT223")
      (libsource (lib "eagle-import") (part "LM1117"))
    )
    (comp (ref "L1")
      (value "68µH")
      (footprint "eagle-import:PISM")
      (libsource (lib "eagle-import") (part "L-EUPISM"))
    )
    (comp (ref "L5")
      (value "100µH")
      (footprint "eagle-import:PISM")
      (libsource (lib "eagle-import") (part "L-EUPISM"))
    )
    (comp (ref "L6")
      (value "150µH")
      (footprint "eagle-import:PISM")
      (libsource (lib "eagle-import") (part "L-EUPISM"))
    )
    (comp (ref "LED4")
      (value "LEDCHIP-LED0805")
      (footprint "eagle-import:CHIP-LED0805")
      (libsource (lib "eagle-import") (part "LEDCHIP-LED0805"))
    )
    (comp (ref "LED5")
      (value "LEDCHIP-LED0805")
      (footprint "eagle-import:CHIP-LED0805")
      (libsource (lib "eagle-import") (part "LEDCHIP-LED0805"))
    )
    (comp (ref "LED6")
      (value "LEDCHIP-LED0805")
      (footprint "eagle-import:CHIP-LED0805")
      (libsource (lib "eagle-import") (part "LEDCHIP-LED0805"))
    )
    (comp (ref "LED7")
      (value "LEDCHIP-LED0805")
      (footprint "eagle-import:CHIP-LED0805")
      (libsource (lib "eagle-import") (part "LEDCHIP-LED0805"))
    )
    (comp (ref "LED10")
      (value "LEDCHIP-LED0805")
      (footprint "eagle-import:CHIP-LED0805")
      (libsource (lib "eagle-import") (part "LEDCHIP-LED0805"))
    )
    (comp (ref "R31")
      (value "50k")
      (footprint "eagle-import:R0805")
      (libsource (lib "eagle-import") (part "R-EU_R0805"))
    )
    (comp (ref "R42")
      (value "680")
      (footprint "eagle-import:R0805")
      (libsource (lib "eagle-import") (part "R-EU_R0805"))
    )
    (comp (ref "R43")
      (value "1,5k")
      (footprint "eagle-import:R0805")
      (libsource (lib "eagle-import") (part "R-EU_R0805"))
    )
    (comp (ref "R44")
      (value "4.7k")
      (footprint "eagle-import:R0805")
      (libsource (lib "eagle-import") (part "R-EU_R0805"))
    )
    (comp (ref "R45")
      (value "1,5k")
      (footprint "eagle-import:R0805")
      (libsource (lib "eagle-import") (part "R-EU_R0805"))
    )
    (comp (ref "R50")
      (value "5,6k")
      (footprint "eagle-import:R0805")
      (libsource (lib "eagle-import") (part "R-EU_R0805"))
    )
    (comp (ref "R59")
      (value "10k")
      (footprint "eagle-import:R0805")
      (libsource (lib "eagle-import") (part "R-EU_R0805"))
    )
    (comp (ref "U$8")
      (value "LM2576")
      (footprint "eagle-import:TO220511")
      (libsource (lib "eagle-import") (part "LM2576"))
    )
    (comp (ref "U3")
      (value "LM2675")
      (footprint "eagle-import:SOIC127P620X175-8N")
      (fields (field (name "MPN") "LM2675M-3.3"))
      (libsource (lib "eagle-import") (part "LM2675M-3.3"))
    )
    (comp (ref "U4")
      (value "LM2675")
      (footprint "eagle-import:SOIC127P620X175-8N")
      (fields (field (name "MPN") "LM2675M-3.3"))
      (libsource (lib "eagle-import") (part "LM2675M-3.3"))
    )
    (comp (ref "X1")
      (value "AK500/2-H")
      (footprint "eagle-import:AK500_2-H")
      (libsource (lib "eagle-import") (part "AK500/2-H"))
    )
    (comp (ref "C33")
      (value "100n")
      (footprint "eagle-import:C0603")
      (libsource (lib "eagle-import") (part "C-EUC0603"))
    )
    (comp (ref "C34")
      (value "100n")
      (footprint "eagle-import:C0603")
      (libsource (lib "eagle-import") (part "C-EUC0603"))
    )
    (comp (ref "C36")
      (value "100n")
      (footprint "eagle-import:C0603")
      (libsource (lib "eagle-import") (part "C-EUC0603"))
    )
    (comp (ref "C37")
      (value "1µ/25V")
      (footprint "eagle-import:SMC_A")
      (libsource (lib "eagle-import") (part "CPOL-EUSMCA"))
    )
    (comp (ref "C39")
      (value "100n")
      (footprint "eagle-import:C0603")
      (libsource (lib "eagle-import") (part "C-EUC0603"))
    )
    (comp (ref "C41")
      (value "100n")
      (footprint "eagle-import:C0603")
      (libsource (lib "eagle-import") (part "C-EUC0603"))
    )
    (comp (ref "C44")
      (value "100n")
      (footprint "eagle-import:C0603")
      (libsource (lib "eagle-import") (part "C-EUC0603"))
    )
    (comp (ref "C45")
      (value "100n")
      (footprint "eagle-import:C0603")
      (libsource (lib "eagle-import") (part "C-EUC0603"))
    )
    (comp (ref "C47")
      (value "100n")
      (footprint "eagle-import:C0603")
      (libsource (lib "eagle-import") (part "C-EUC0603"))
    )
    (comp (ref "D14")
      (value "BZX84-A5V1")
      (footprint "eagle-import:TO236")
      (libsource (lib "eagle-import") (part "BZX84CSMD"))
    )
    (comp (ref "IC2")
      (value "4043D")
      (footprint "eagle-import:SO16")
      (libsource (lib "eagle-import") (part "4043D"))
    )
    (comp (ref "IC4")
      (value "LM1458D")
      (footprint "eagle-import:SO08")
      (libsource (lib "eagle-import") (part "1458DLM"))
    )
    (comp (ref "R5")
      (value "10k, 1%")
      (footprint "eagle-import:R0805")
      (libsource (lib "eagle-import") (part "R-EU_R0805"))
    )
    (comp (ref "R21")
      (value "33k, 1%")
      (footprint "eagle-import:R0805")
      (libsource (lib "eagle-import") (part "R-EU_R0805"))
    )
    (comp (ref "R22")
      (value "10k")
      (footprint "eagle-import:R0805")
      (libsource (lib "eagle-import") (part "R-EU_R0805"))
    )
    (comp (ref "R25")
      (value "100k")
      (footprint "eagle-import:R0805")
      (libsource (lib "eagle-import") (part "R-EU_R0805"))
    )
    (comp (ref "R26")
      (value "50k")
      (footprint "eagle-import:R0805")
      (libsource (lib "eagle-import") (part "R-EU_R0805"))
    )
    (comp (ref "R30")
      (value "3.3k")
      (footprint "eagle-import:R0805")
      (libsource (lib "eagle-import") (part "R-EU_R0805"))
    )
    (comp (ref "R52")
      (value "5,6k, 1%")
      (footprint "eagle-import:R0805")
      (libsource (lib "eagle-import") (part "R-EU_R0805"))
    )
    (comp (ref "R58")
      (value "10k")
      (footprint "eagle-import:R0805")
      (libsource (lib "eagle-import") (part "R-EU_R0805"))
    )
    (comp (ref "S1")
      (value "10-XX")
      (footprint "eagle-import:B3F-10XX")
      (libsource (lib "eagle-import") (part "10-XX"))
    )
    (comp (ref "T4")
      (value "BC849")
      (footprint "eagle-import:SOT23")
      (libsource (lib "eagle-import") (part "BC849"))
    )
    (comp (ref "U2")
      (value "SN74LVC2G02DCTR")
      (footprint "eagle-import:SOP65P400X130-8N")
      (libsource (lib "eagle-import") (part "SN74LVC2G02DCTR"))
    )
    (comp (ref "C9")
      (value "2200µ/50V")
      (footprint "eagle-import:E5-13")
      (libsource (lib "eagle-import") (part "CPOL-EUE5-13"))
    )
    (comp (ref "C10")
      (value "2200µ/50V")
      (footprint "eagle-import:E5-13")
      (libsource (lib "eagle-import") (part "CPOL-EUE5-13"))
    )
    (comp (ref "C11")
      (value "100n")
      (footprint "eagle-import:C0603")
      (libsource (lib "eagle-import") (part "C-EUC0603"))
    )
    (comp (ref "C12")
      (value "100n")
      (footprint "eagle-import:C0603")
      (libsource (lib "eagle-import") (part "C-EUC0603"))
    )
    (comp (ref "C13")
      (value "2.2µ/250V")
      (footprint "eagle-import:C2220K")
      (libsource (lib "eagle-import") (part "C-EUC2220K"))
    )
    (comp (ref "C25")
      (value "10µ/450V")
      (footprint "eagle-import:E5-10,5")
      (libsource (lib "eagle-import") (part "CPOL-EUE5-10.5"))
    )
    (comp (ref "C35")
      (value "1µ/50V")
      (footprint "eagle-import:C1206")
      (libsource (lib "eagle-import") (part "C-EUC1206"))
    )
    (comp (ref "C48")
      (value "100n")
      (footprint "eagle-import:C0603")
      (libsource (lib "eagle-import") (part "C-EUC0603"))
    )
    (comp (ref "C49")
      (value "10µ/10V")
      (footprint "eagle-import:C0603")
      (libsource (lib "eagle-import") (part "C-EUC0603"))
    )
    (comp (ref "C50")
      (value "1µ/50V")
      (footprint "eagle-import:C1206")
      (libsource (lib "eagle-import") (part "C-EUC1206"))
    )
    (comp (ref "CAP_0V")
      (value "WIREPADSMD5-5")
      (footprint "eagle-import:5-5")
      (libsource (lib "eagle-import") (part "WIREPADSMD5-5"))
    )
    (comp (ref "CAP_330V")
      (value "WIREPADSMD5-5")
      (footprint "eagle-import:5-5")
      (libsource (lib "eagle-import") (part "WIREPADSMD5-5"))
    )
    (comp (ref "CF")
      (value "470p")
      (footprint "eagle-import:C0603")
      (libsource (lib "eagle-import") (part "C-EUC0603"))
    )
    (comp (ref "CSS")
      (value "1µ/10V")
      (footprint "eagle-import:C0603")
      (libsource (lib "eagle-import") (part "C-EUC0603"))
    )
    (comp (ref "C_BOOT")
      (value "100n")
      (footprint "eagle-import:C0603")
      (libsource (lib "eagle-import") (part "C-EUC0603"))
    )
    (comp (ref "C_DELAY")
      (value "1µ/10V")
      (footprint "eagle-import:C0603")
      (libsource (lib "eagle-import") (part "C-EUC0603"))
    )
    (comp (ref "C_ISEN_A")
      (value "10n/50V")
      (footprint "eagle-import:C0603")
      (libsource (lib "eagle-import") (part "C-EUC0603"))
    )
    (comp (ref "C_ISEN_B")
      (value "24nF/10V")
      (footprint "eagle-import:C0603")
      (libsource (lib "eagle-import") (part "C-EUC0603"))
    )
    (comp (ref "D3")
      (value "MBR0520LT")
      (footprint "eagle-import:SOD123")
      (libsource (lib "eagle-import") (part "MBR0520LT"))
    )
    (comp (ref "D4")
      (value "MBR0520LT")
      (footprint "eagle-import:SOD123")
      (libsource (lib "eagle-import") (part "MBR0520LT"))
    )
    (comp (ref "D8")
      (value "STTH1R06A")
      (footprint "eagle-import:SMA-DO214AC")
      (libsource (lib "eagle-import") (part "GF1"))
    )
    (comp (ref "D9")
      (value "STTH1R06A")
      (footprint "eagle-import:SMA-DO214AC")
      (libsource (lib "eagle-import") (part "GF1"))
    )
    (comp (ref "D10")
      (value "STTH1R06A")
      (footprint "eagle-import:SMA-DO214AC")
      (libsource (lib "eagle-import") (part "GF1"))
    )
    (comp (ref "D11")
      (value "STTH1R06A")
      (footprint "eagle-import:SMA-DO214AC")
      (libsource (lib "eagle-import") (part "GF1"))
    )
    (comp (ref "D13")
      (value "SMD ZD 12")
      (footprint "eagle-import:TO236")
      (libsource (lib "eagle-import") (part "BZX84CSMD"))
    )
    (comp (ref "L3")
      (value "3.3UH")
      (footprint "eagle-import:IND_ELLATP-B")
      (fields (field (name "MPN") "ELLATP3R3NB"))
      (libsource (lib "eagle-import") (part "ELL-ATP-BATP3R3NB"))
    )
    (comp (ref "L4")
      (value "820n")
      (footprint "eagle-import:WE-HCI_1890")
      (libsource (lib "eagle-import") (part "WE-HCI_1890"))
    )
    (comp (ref "L7")
      (value "WE-LLCR")
      (footprint "eagle-import:WE-LLCR_ETD34")
      (libsource (lib "eagle-import") (part "WE-LLCR_ETD34"))
    )
    (comp (ref "LED8")
      (value "LEDCHIP-LED0805")
      (footprint "eagle-import:CHIP-LED0805")
      (libsource (lib "eagle-import") (part "LEDCHIP-LED0805"))
    )
    (comp (ref "Q3")
      (value "IPP023N10N5")
      (footprint "eagle-import:TO220BV")
      (libsource (lib "eagle-import") (part "PMOSFET_NTO220BV"))
    )
    (comp (ref "Q4")
      (value "IPP023N10N5")
      (footprint "eagle-import:TO220BV")
      (libsource (lib "eagle-import") (part "PMOSFET_NTO220BV"))
    )
    (comp (ref "Q5")
      (value "IPD90P04P4L")
      (footprint "eagle-import:D-PAK_TO252AA")
      (libsource (lib "eagle-import") (part "IRF?5305R"))
    )
    (comp (ref "R23")
      (value "NTC644A")
      (footprint "eagle-import:N644A")
      (libsource (lib "eagle-import") (part "NTC644A"))
    )
    (comp (ref "R24")
      (value "5,6k")
      (footprint "eagle-import:R0805")
      (libsource (lib "eagle-import") (part "R-EU_R0805"))
    )
    (comp (ref "R27")
      (value "50k")
      (footprint "eagle-import:R0805")
      (libsource (lib "eagle-import") (part "R-EU_R0805"))
    )
    (comp (ref "R28")
      (value "5,6k")
      (footprint "eagle-import:R0805")
      (libsource (lib "eagle-import") (part "R-EU_R0805"))
    )
    (comp (ref "R46")
      (value "10k")
      (footprint "eagle-import:R0805")
      (libsource (lib "eagle-import") (part "R-EU_R0805"))
    )
    (comp (ref "R48")
      (value "5,6k")
      (footprint "eagle-import:R0805")
      (libsource (lib "eagle-import") (part "R-EU_R0805"))
    )
    (comp (ref "R53")
      (value "100k")
      (footprint "eagle-import:R0805")
      (libsource (lib "eagle-import") (part "R-EU_R0805"))
    )
    (comp (ref "R54")
      (value "100k")
      (footprint "eagle-import:R0805")
      (libsource (lib "eagle-import") (part "R-EU_R0805"))
    )
    (comp (ref "R200")
      (value "50k")
      (footprint "eagle-import:R0805")
      (libsource (lib "eagle-import") (part "R-EU_R0805"))
    )
    (comp (ref "RF_MAX")
      (value "33k")
      (footprint "eagle-import:R0805")
      (libsource (lib "eagle-import") (part "R-EU_R0805"))
    )
    (comp (ref "RF_MIN")
      (value "12k")
      (footprint "eagle-import:R0805")
      (libsource (lib "eagle-import") (part "R-EU_R0805"))
    )
    (comp (ref "R_DELAY")
      (value "33k")
      (footprint "eagle-import:R0805")
      (libsource (lib "eagle-import") (part "R-EU_R0805"))
    )
    (comp (ref "R_ISEN_A")
      (value "33k")
      (footprint "eagle-import:R0805")
      (libsource (lib "eagle-import") (part "R-EU_R0805"))
    )
    (comp (ref "R_ISEN_B")
      (value "6,8k")
      (footprint "eagle-import:R0805")
      (libsource (lib "eagle-import") (part "R-EU_R0805"))
    )
    (comp (ref "R_SS")
      (value "3.3k, 1%")
      (footprint "eagle-import:R0805")
      (libsource (lib "eagle-import") (part "R-EU_R0805"))
    )
    (comp (ref "T3")
      (value "BC849")
      (footprint "eagle-import:SOT23")
      (libsource (lib "eagle-import") (part "BC849"))
    )
    (comp (ref "T8")
      (value "BC849")
      (footprint "eagle-import:SOT23")
      (libsource (lib "eagle-import") (part "BC849"))
    )
    (comp (ref "U$3")
      (value "L6599")
      (footprint "eagle-import:SO16")
      (libsource (lib "eagle-import") (part "L6599"))
    )
    (comp (ref "X2")
      (value "AK500/2-H")
      (footprint "eagle-import:AK500_2-H")
      (libsource (lib "eagle-import") (part "AK500/2-H"))
    )
    (comp (ref "C26")
      (value "100n")
      (footprint "eagle-import:C0603")
      (libsource (lib "eagle-import") (part "C-EUC0603"))
    )
    (comp (ref "C27")
      (value "100n")
      (footprint "eagle-import:C0603")
      (libsource (lib "eagle-import") (part "C-EUC0603"))
    )
    (comp (ref "C28")
      (value "100n")
      (footprint "eagle-import:C0603")
      (libsource (lib "eagle-import") (part "C-EUC0603"))
    )
    (comp (ref "JP1")
      (value "PINHD-1X5")
      (footprint "eagle-import:1X05")
      (libsource (lib "eagle-import") (part "PINHD-1X5"))
    )
    (comp (ref "JP2")
      (value "PINHD-1X5")
      (footprint "eagle-import:1X05")
      (libsource (lib "eagle-import") (part "PINHD-1X5"))
    )
    (comp (ref "R1")
      (value "1k")
      (footprint "eagle-import:R0805")
      (libsource (lib "eagle-import") (part "R-EU_R0805"))
    )
    (comp (ref "R32")
      (value "120")
      (footprint "eagle-import:R0805")
      (libsource (lib "eagle-import") (part "R-EU_R0805"))
    )
    (comp (ref "RJ_1")
      (value "RJ10")
      (footprint "eagle-import:RJ10")
      (libsource (lib "eagle-import") (part "RJ10"))
    )
    (comp (ref "RJ_2")
      (value "RJ10")
      (footprint "eagle-import:RJ10")
      (libsource (lib "eagle-import") (part "RJ10"))
    )
    (comp (ref "SJ1") (value "SJ") (footprint "eagle-import:SJ") (libsource (lib "eagle-import") (part "SJ")))
    (comp (ref "U$1")
      (value "MCP2551-I/SN")
      (footprint "eagle-import:SOIC127P600X175-8N")
      (libsource (lib "eagle-import") (part "MCP2551-I/SN"))
    )
    (comp (ref "U1")
      (value "TXB0108PWR")
      (footprint "eagle-import:SOP65P640X120-20N")
      (libsource (lib "eagle-import") (part "TXB0108PWR"))
    )
  )
  (nets
    (net (code "1") (name "+3V3") (class "Default")
      (node (ref "C2") (pin "1") (pinfunction "1_1") (pintype "passive"))
      (node (ref "C27") (pin "1") (pinfunction "1_1") (pintype "passive"))
      (node (ref "D2") (pin "A") (pinfunction "A_A") (pintype "passive"))
      (node (ref "IC3") (pin "2") (pinfunction "OUT_2") (pintype "passive"))
      (node (ref "IC3") (pin "4") (pinfunction "OUT_4") (pintype "input"))
      (node (ref "JP2") (pin "4") (pinfunction "4_4") (pintype "passive"))
      (node (ref "R42") (pin "2") (pinfunction "2_2") (pintype "passive"))
      (node (ref "U1") (pin "10") (pinfunction "OE_10") (pintype "input"))
      (node (ref "U1") (pin "2") (pinfunction "VCCA_2") (pintype "power_in"))
    )
    (net (code "2") (name "+5V") (class "Default")
      (node (ref "C1") (pin "1") (pinfunction "1_1") (pintype "passive"))
      (node (ref "C18") (pin "+") (pinfunction "+_+") (pintype "passive"))
      (node (ref "C26") (pin "1") (pinfunction "1_1") (pintype "passive"))
      (node (ref "C28") (pin "1") (pinfunction "1_1") (pintype "passive"))
      (node (ref "C34") (pin "1") (pinfunction "1_1") (pintype "passive"))
      (node (ref "C44") (pin "1") (pinfunction "1_1") (pintype "passive"))
      (node (ref "C45") (pin "1") (pinfunction "1_1") (pintype "passive"))
      (node (ref "C8") (pin "2") (pinfunction "2_2") (pintype "passive"))
      (node (ref "D2") (pin "K") (pinfunction "C_K") (pintype "passive"))
      (node (ref "IC2") (pin "16") (pinfunction "VDD_16") (pintype "power_in"))
      (node (ref "IC3") (pin "3") (pinfunction "IN_3") (pintype "input"))
      (node (ref "IC4") (pin "8") (pinfunction "V+_8") (pintype "power_in"))
      (node (ref "L5") (pin "1") (pinfunction "1_1") (pintype "passive"))
      (node (ref "OK2") (pin "8") (pinfunction "COL_8") (pintype "passive"))
      (node (ref "R17") (pin "2") (pinfunction "2_2") (pintype "passive"))
      (node (ref "R26") (pin "2") (pinfunction "2_2") (pintype "passive"))
      (node (ref "R43") (pin "2") (pinfunction "2_2") (pintype "passive"))
      (node (ref "R58") (pin "2") (pinfunction "2_2") (pintype "passive"))
      (node (ref "R70") (pin "1") (pinfunction "1_1") (pintype "passive"))
      (node (ref "S1") (pin "1") (pinfunction "S_1") (pintype "passive"))
      (node (ref "S1") (pin "2") (pinfunction "S1_2") (pintype "passive"))
      (node (ref "SV1") (pin "2") (pinfunction "2_2") (pintype "passive"))
      (node (ref "U$1") (pin "3") (pinfunction "VDD_3") (pintype "power_in"))
      (node (ref "U$2") (pin "4") (pinfunction "VCC_4") (pintype "bidirectional"))
      (node (ref "U1") (pin "19") (pinfunction "VCCB_19") (pintype "power_in"))
      (node (ref "U2") (pin "8") (pinfunction "VCC_8") (pintype "power_in"))
      (node (ref "U3") (pin "4") (pinfunction "FB_4") (pintype "input"))
    )
    (net (code "3") (name "+5V{slash}1") (class "Default")
      (node (ref "C40") (pin "+") (pinfunction "+_+") (pintype "passive"))
      (node (ref "JP3") (pin "2") (pinfunction "2_2") (pintype "passive"))
      (node (ref "JP4") (pin "2") (pinfunction "2_2") (pintype "passive"))
      (node (ref "L1") (pin "1") (pinfunction "1_1") (pintype "passive"))
      (node (ref "R45") (pin "2") (pinfunction "2_2") (pintype "passive"))
      (node (ref "U$8") (pin "4") (pinfunction "FB_4") (pintype "bidirectional"))
    )
    (net (code "4") (name "+5V{slash}3") (class "Default")
      (node (ref "C37") (pin "+") (pinfunction "+_+") (pintype "passive"))
      (node (ref "C39") (pin "1") (pinfunction "1_1") (pintype "passive"))
      (node (ref "C7") (pin "2") (pinfunction "2_2") (pintype "passive"))
      (node (ref "D14") (pin "C") (pinfunction "C_C") (pintype "passive"))
      (node (ref "OK1") (pin "6") (pinfunction "COL_6") (pintype "passive"))
      (node (ref "R30") (pin "1") (pinfunction "1_1") (pintype "passive"))
      (node (ref "R5") (pin "2") (pinfunction "2_2") (pintype "passive"))
      (node (ref "U$2") (pin "19") (pinfunction "AVCC_19") (pintype "bidirectional"))
    )
    (net (code "5") (name "+5V{slash}4") (class "Default")
      (node (ref "C16") (pin "1") (pinfunction "1_1") (pintype "passive"))
      (node (ref "C38") (pin "+") (pinfunction "+_+") (pintype "passive"))
      (node (ref "D12") (pin "C") (pinfunction "C_C") (pintype "passive"))
      (node (ref "OK1") (pin "8") (pinfunction "COL_8") (pintype "passive"))
      (node (ref "R29") (pin "1") (pinfunction "1_1") (pintype "passive"))
      (node (ref "R7") (pin "2") (pinfunction "2_2") (pintype "passive"))
    )
    (net (code "6") (name "+12V") (class "Default")
      (node (ref "C11") (pin "1") (pinfunction "1_1") (pintype "passive"))
      (node (ref "C21") (pin "+") (pinfunction "+_+") (pintype "passive"))
      (node (ref "L6") (pin "1") (pinfunction "1_1") (pintype "passive"))
      (node (ref "R44") (pin "2") (pinfunction "2_2") (pintype "passive"))
      (node (ref "U$3") (pin "12") (pinfunction "VCC_12") (pintype "bidirectional"))
      (node (ref "U4") (pin "4") (pinfunction "FB_4") (pintype "input"))
    )
    (net (code "7") (name "+24V") (class "Default")
      (node (ref "C17") (pin "+") (pinfunction "+_+") (pintype "passive"))
      (node (ref "C20") (pin "+") (pinfunction "+_+") (pintype "passive"))
      (node (ref "C3") (pin "+") (pinfunction "+_+") (pintype "passive"))
      (node (ref "C42") (pin "+") (pinfunction "+_+") (pintype "passive"))
      (node (ref "D1") (pin "K") (pinfunction "C_K") (pintype "passive"))
      (node (ref "F1") (pin "1") (pinfunction "1_1") (pintype "passive"))
      (node (ref "R30") (pin "2") (pinfunction "2_2") (pintype "passive"))
      (node (ref "R31") (pin "1") (pinfunction "1_1") (pintype "passive"))
      (node (ref "U$4") (pin "1") (pinfunction "U_IN_1") (pintype "bidirectional"))
      (node (ref "U$8") (pin "1") (pinfunction "VIN_1") (pintype "bidirectional"))
      (node (ref "U3") (pin "7") (pinfunction "VIN_7") (pintype "power_in"))
      (node (ref "U4") (pin "7") (pinfunction "VIN_7") (pintype "power_in"))
    )
    (net (code "8") (name "24V_PRI") (class "Default")
      (node (ref "C10") (pin "+") (pinfunction "+_+") (pintype "passive"))
      (node (ref "C35") (pin "1") (pinfunction "1_1") (pintype "passive"))
      (node (ref "C50") (pin "1") (pinfunction "1_1") (pintype "passive"))
      (node (ref "C9") (pin "+") (pinfunction "+_+") (pintype "passive"))
      (node (ref "Q3") (pin "D") (pinfunction "D_D") (pintype "passive"))
      (node (ref "Q5") (pin "4") (pinfunction "D_4") (pintype "passive"))
      (node (ref "R23") (pin "2") (pinfunction "2_2") (pintype "passive"))
      (node (ref "R27") (pin "2") (pinfunction "2_2") (pintype "passive"))
    )
    (net (code "9") (name "ACTIVATE_BOOSTER") (class "Default")
      (node (ref "R24") (pin "1") (pinfunction "1_1") (pintype "passive"))
      (node (ref "R25") (pin "1") (pinfunction "1_1") (pintype "passive"))
      (node (ref "U$2") (pin "26") (pinfunction "PB5_26") (pintype "bidirectional"))
    )
    (net (code "10") (name "ACTIVATE_SERVO") (class "Default")
      (node (ref "R47") (pin "1") (pinfunction "1_1") (pintype "passive"))
      (node (ref "U$2") (pin "15") (pinfunction "PD7_15") (pintype "bidirectional"))
    )
    (net (code "11") (name "ADC9{slash}FREI") (class "Default")
      (node (ref "U$2") (pin "18") (pinfunction "PC5_18") (pintype "bidirectional"))
    )
    (net (code "12") (name "ADC_24V_LOGIK{slash}SCK_A") (class "Default")
      (node (ref "R31") (pin "2") (pinfunction "2_2") (pintype "passive"))
      (node (ref "R50") (pin "1") (pinfunction "1_1") (pintype "passive"))
      (node (ref "SV1") (pin "7") (pinfunction "7_7") (pintype "passive"))
      (node (ref "U$2") (pin "12") (pinfunction "(RXD)PD4_12") (pintype "bidirectional"))
    )
    (net (code "13") (name "ADC_24V_PRI") (class "Default")
      (node (ref "R27") (pin "1") (pinfunction "1_1") (pintype "passive"))
      (node (ref "R28") (pin "2") (pinfunction "2_2") (pintype "passive"))
      (node (ref "U$2") (pin "13") (pinfunction "PD5_13") (pintype "bidirectional"))
    )
    (net (code "14") (name "ADC_CAP") (class "Default")
      (node (ref "C23") (pin "1") (pinfunction "1_1") (pintype "passive"))
      (node (ref "C47") (pin "1") (pinfunction "1_1") (pintype "passive"))
      (node (ref "IC4") (pin "3") (pinfunction "+IN_3") (pintype "input"))
      (node (ref "OK1") (pin "5") (pinfunction "EMIT_5") (pintype "passive"))
      (node (ref "R8") (pin "2") (pinfunction "2_2") (pintype "passive"))
      (node (ref "U$2") (pin "14") (pinfunction "PD6_14") (pintype "bidirectional"))
    )
    (net (code "15") (name "BOOSTER_24V") (class "Default")
      (node (ref "Q5") (pin "3") (pinfunction "S_3") (pintype "passive"))
      (node (ref "R200") (pin "2") (pinfunction "2_2") (pintype "passive"))
      (node (ref "R23") (pin "1") (pinfunction "1_1") (pintype "passive"))
      (node (ref "R46") (pin "2") (pinfunction "2_2") (pintype "passive"))
      (node (ref "X2") (pin "2") (pinfunction "KL_2") (pintype "passive"))
    )
    (net (code "16") (name "CAN_H") (class "Default")
      (node (ref "RJ_1") (pin "P$3") (pinfunction "P$3_P$3") (pintype "bidirectional"))
      (node (ref "RJ_2") (pin "P$3") (pinfunction "P$3_P$3") (pintype "bidirectional"))
      (node (ref "SJ1") (pin "2") (pinfunction "2_2") (pintype "passive"))
      (node (ref "U$1") (pin "7") (pinfunction "CANH_7") (pintype "bidirectional"))
    )
    (net (code "17") (name "CAN_L") (class "Default")
      (node (ref "R32") (pin "2") (pinfunction "2_2") (pintype "passive"))
      (node (ref "RJ_1") (pin "P$2") (pinfunction "P$2_P$2") (pintype "bidirectional"))
      (node (ref "RJ_2") (pin "P$2") (pinfunction "P$2_P$2") (pintype "bidirectional"))
      (node (ref "U$1") (pin "6") (pinfunction "CANL_6") (pintype "bidirectional"))
    )
    (net (code "18") (name "CAN_RX") (class "Default")
      (node (ref "U$1") (pin "4") (pinfunction "RXD_4") (pintype "output"))
      (node (ref "U$2") (pin "7") (pinfunction "(RXCAN)PC3_7") (pintype "bidirectional"))
    )
    (net (code "19") (name "CAN_TX") (class "Default")
      (node (ref "U$1") (pin "1") (pinfunction "TXD_1") (pintype "input"))
      (node (ref "U$2") (pin "6") (pinfunction "(TXCAN)PC2_6") (pintype "bidirectional"))
    )
    (net (code "20") (name "CAP_+12V") (class "Default")
      (node (ref "C29") (pin "+") (pinfunction "+_+") (pintype "passive"))
      (node (ref "C30") (pin "+") (pinfunction "+_+") (pintype "passive"))
      (node (ref "C31") (pin "+") (pinfunction "+_+") (pintype "passive"))
      (node (ref "C43") (pin "1") (pinfunction "1_1") (pintype "passive"))
      (node (ref "IC1") (pin "8") (pinfunction "V+_8") (pintype "power_in"))
      (node (ref "R29") (pin "2") (pinfunction "2_2") (pintype "passive"))
      (node (ref "R39") (pin "2") (pinfunction "2_2") (pintype "passive"))
      (node (ref "R40") (pin "2") (pinfunction "2_2") (pintype "passive"))
      (node (ref "R41") (pin "2") (pinfunction "2_2") (pintype "passive"))
      (node (ref "R49") (pin "2") (pinfunction "2_2") (pintype "passive"))
      (node (ref "T6") (pin "E") (pinfunction "E_E") (pintype "passive"))
      (node (ref "U$4") (pin "6") (pinfunction "+U_OUT_6") (pintype "bidirectional"))
      (node (ref "U$5") (pin "8") (pinfunction "VDD_8") (pintype "bidirectional"))
      (node (ref "U$6") (pin "8") (pinfunction "VDD_8") (pintype "bidirectional"))
    )
    (net (code "21") (name "CAP_0V") (class "Default")
      (node (ref "C14") (pin "2") (pinfunction "2_2") (pintype "passive"))
      (node (ref "C15") (pin "2") (pinfunction "2_2") (pintype "passive"))
      (node (ref "C16") (pin "2") (pinfunction "2_2") (pintype "passive"))
      (node (ref "C25") (pin "-") (pinfunction "-_-") (pintype "passive"))
      (node (ref "C29") (pin "-") (pinfunction "-_-") (pintype "passive"))
      (node (ref "C30") (pin "-") (pinfunction "-_-") (pintype "passive"))
      (node (ref "C31") (pin "-") (pinfunction "-_-") (pintype "passive"))
      (node (ref "C32") (pin "2") (pinfunction "2_2") (pintype "passive"))
      (node (ref "C38") (pin "-") (pinfunction "-_-") (pintype "passive"))
      (node (ref "C43") (pin "2") (pinfunction "2_2") (pintype "passive"))
      (node (ref "C46") (pin "2") (pinfunction "2_2") (pintype "passive"))
      (node (ref "C51") (pin "2") (pinfunction "2_2") (pintype "passive"))
      (node (ref "CAP_0V") (pin "P$1") (pinfunction "P_P$1") (pintype "passive"))
      (node (ref "D10") (pin "A") (pinfunction "A_A") (pintype "passive"))
      (node (ref "D11") (pin "A") (pinfunction "A_A") (pintype "passive"))
      (node (ref "D12") (pin "A") (pinfunction "A_A") (pintype "passive"))
      (node (ref "H1") (pin "B3,0") (pinfunction "MOUNT_B3,0") (pintype "passive"))
      (node (ref "IC1") (pin "4") (pinfunction "V-_4") (pintype "power_in"))
      (node (ref "LED9") (pin "C") (pinfunction "C_C") (pintype "passive"))
      (node (ref "OK1") (pin "4") (pinfunction "C_4") (pintype "passive"))
      (node (ref "OK2") (pin "2") (pinfunction "C_2") (pintype "passive"))
      (node (ref "Q2") (pin "S") (pinfunction "S_S") (pintype "passive"))
      (node (ref "Q6") (pin "S") (pinfunction "S_S") (pintype "passive"))
      (node (ref "R11") (pin "1") (pinfunction "1_1") (pintype "passive"))
      (node (ref "R12") (pin "1") (pinfunction "1_1") (pintype "passive"))
      (node (ref "R20") (pin "1") (pinfunction "1_1") (pintype "passive"))
      (node (ref "R36") (pin "1") (pinfunction "1_1") (pintype "passive"))
      (node (ref "R37") (pin "1") (pinfunction "1_1") (pintype "passive"))
      (node (ref "R38") (pin "1") (pinfunction "1_1") (pintype "passive"))
      (node (ref "R4") (pin "1") (pinfunction "1_1") (pintype "passive"))
      (node (ref "R6") (pin "1") (pinfunction "1_1") (pintype "passive"))
      (node (ref "U$4") (pin "4") (pinfunction "-U_OUT_4") (pintype "bidirectional"))
      (node (ref "U$5") (pin "5") (pinfunction "GND_5") (pintype "bidirectional"))
      (node (ref "U$6") (pin "5") (pinfunction "GND_5") (pintype "bidirectional"))
      (node (ref "VR1") (pin "3") (pinfunction "A_3") (pintype "passive"))
      (node (ref "VR2") (pin "3") (pinfunction "A_3") (pintype "passive"))
      (node (ref "VR3") (pin "3") (pinfunction "A_3") (pintype "passive"))
    )
    (net (code "22") (name "CAP_330V") (class "Default")
      (node (ref "C25") (pin "+") (pinfunction "+_+") (pintype "passive"))
      (node (ref "CAP_330V") (pin "P$1") (pinfunction "P_P$1") (pintype "passive"))
      (node (ref "COIL_OUT") (pin "P$1") (pinfunction "P_P$1") (pintype "passive"))
      (node (ref "D8") (pin "K") (pinfunction "C_K") (pintype "passive"))
      (node (ref "D9") (pin "K") (pinfunction "C_K") (pintype "passive"))
      (node (ref "R101") (pin "2") (pinfunction "2_2") (pintype "passive"))
      (node (ref "R2") (pin "1") (pinfunction "1_1") (pintype "passive"))
      (node (ref "R33") (pin "2") (pinfunction "2_2") (pintype "passive"))
      (node (ref "R34") (pin "2") (pinfunction "2_2") (pintype "passive"))
      (node (ref "R35") (pin "2") (pinfunction "2_2") (pintype "passive"))
      (node (ref "U$7") (pin "C") (pinfunction "C_C") (pintype "passive"))
    )
    (net (code "23") (name "CLKOUT_ETH") (class "Default")
      (node (ref "U1") (pin "12") (pinfunction "B8_12") (pintype "bidirectional"))
    )
    (net (code "24") (name "CLKOUT_ETH_3V") (class "Default")
      (node (ref "JP2") (pin "1") (pinfunction "1_1") (pintype "passive"))
      (node (ref "U1") (pin "9") (pinfunction "A8_9") (pintype "bidirectional"))
    )
    (net (code "25") (name "CS_ETH") (class "Default")
      (node (ref "U$2") (pin "29") (pinfunction "PD0_29") (pintype "bidirectional"))
      (node (ref "U1") (pin "13") (pinfunction "B7_13") (pintype "bidirectional"))
    )
    (net (code "26") (name "CS_ETH_3V") (class "Default")
      (node (ref "JP2") (pin "2") (pinfunction "2_2") (pintype "passive"))
      (node (ref "U1") (pin "8") (pinfunction "A7_8") (pintype "bidirectional"))
    )
    (net (code "27") (name "D2A") (class "Default")
      (node (ref "R52") (pin "1") (pinfunction "1_1") (pintype "passive"))
      (node (ref "U$2") (pin "25") (pinfunction "PC7_25") (pintype "bidirectional"))
    )
    (net (code "28") (name "FREI") (class "Default")
      (node (ref "U$2") (pin "16") (pinfunction "PB2_16") (pintype "bidirectional"))
    )
    (net (code "29") (name "FREI2") (class "Default")
      (node (ref "U$2") (pin "27") (pinfunction "PB6_27") (pintype "bidirectional"))
    )
    (net (code "30") (name "GND") (class "Default")
      (node (ref "C1") (pin "2") (pinfunction "2_2") (pintype "passive"))
      (node (ref "C11") (pin "2") (pinfunction "2_2") (pintype "passive"))
      (node (ref "C12") (pin "2") (pinfunction "2_2") (pintype "passive"))
      (node (ref "C17") (pin "-") (pinfunction "-_-") (pintype "passive"))
      (node (ref "C18") (pin "-") (pinfunction "-_-") (pintype "passive"))
      (node (ref "C2") (pin "2") (pinfunction "2_2") (pintype "passive"))
      (node (ref "C20") (pin "-") (pinfunction "-_-") (pintype "passive"))
      (node (ref "C21") (pin "-") (pinfunction "-_-") (pintype "passive"))
      (node (ref "C23") (pin "2") (pinfunction "2_2") (pintype "passive"))
      (node (ref "C24") (pin "2") (pinfunction "2_2") (pintype "passive"))
      (node (ref "C26") (pin "2") (pinfunction "2_2") (pintype "passive"))
      (node (ref "C27") (pin "2") (pinfunction "2_2") (pintype "passive"))
      (node (ref "C28") (pin "2") (pinfunction "2_2") (pintype "passive"))
      (node (ref "C3") (pin "-") (pinfunction "-_-") (pintype "passive"))
      (node (ref "C33") (pin "2") (pinfunction "2_2") (pintype "passive"))
      (node (ref "C34") (pin "2") (pinfunction "2_2") (pintype "passive"))
      (node (ref "C36") (pin "2") (pinfunction "2_2") (pintype "passive"))
      (node (ref "C37") (pin "-") (pinfunction "-_-") (pintype "passive"))
      (node (ref "C39") (pin "2") (pinfunction "2_2") (pintype "passive"))
      (node (ref "C4") (pin "1") (pinfunction "1_1") (pintype "passive"))
      (node (ref "C40") (pin "-") (pinfunction "-_-") (pintype "passive"))
      (node (ref "C41") (pin "2") (pinfunction "2_2") (pintype "passive"))
      (node (ref "C42") (pin "-") (pinfunction "-_-") (pintype "passive"))
      (node (ref "C44") (pin "2") (pinfunction "2_2") (pintype "passive"))
      (node (ref "C45") (pin "2") (pinfunction "2_2") (pintype "passive"))
      (node (ref "C47") (pin "2") (pinfunction "2_2") (pintype "passive"))
      (node (ref "C48") (pin "2") (pinfunction "2_2") (pintype "passive"))
      (node (ref "C49") (pin "2") (pinfunction "2_2") (pintype "passive"))
      (node (ref "C5") (pin "1") (pinfunction "1_1") (pintype "passive"))
      (node (ref "C6") (pin "1") (pinfunction "1_1") (pintype "passive"))
      (node (ref "C7") (pin "1") (pinfunction "1_1") (pintype "passive"))
      (node (ref "C8") (pin "1") (pinfunction "1_1") (pintype "passive"))
      (node (ref "CF") (pin "2") (pinfunction "2_2") (pintype "passive"))
      (node (ref "CSS") (pin "2") (pinfunction "2_2") (pintype "passive"))
      (node (ref "C_DELAY") (pin "2") (pinfunction "2_2") (pintype "passive"))
      (node (ref "C_ISEN_B") (pin "2") (pinfunction "2_2") (pintype "passive"))
      (node (ref "D1") (pin "A") (pinfunction "A_A") (pintype "passive"))
      (node (ref "D14") (pin "A") (pinfunction "A_A") (pintype "passive"))
      (node (ref "D15") (pin "A") (pinfunction "A_A") (pintype "passive"))
      (node (ref "D4") (pin "A") (pinfunction "A_A") (pintype "passive"))
      (node (ref "D6") (pin "A") (pinfunction "A_A") (pintype "passive"))
      (node (ref "D7") (pin "A") (pinfunction "A_A") (pintype "passive"))
      (node (ref "H2") (pin "B3,0") (pinfunction "MOUNT_B3,0") (pintype "passive"))
      (node (ref "H3") (pin "B3,0") (pinfunction "MOUNT_B3,0") (pintype "passive"))
      (node (ref "H4") (pin "B3,0") (pinfunction "MOUNT_B3,0") (pintype "passive"))
      (node (ref "IC2") (pin "3") (pinfunction "R0_3") (pintype "input"))
      (node (ref "IC2") (pin "4") (pinfunction "S0_4") (pintype "input"))
      (node (ref "IC2") (pin "6") (pinfunction "S1_6") (pintype "input"))
      (node (ref "IC2") (pin "7") (pinfunction "R1_7") (pintype "input"))
      (node (ref "IC2") (pin "8") (pinfunction "VSS_8") (pintype "power_in"))
      (node (ref "IC3") (pin "1") (pinfunction "GND_1") (pintype "input"))
      (node (ref "IC4") (pin "4") (pinfunction "V-_4") (pintype "power_in"))
      (node (ref "IC4") (pin "5") (pinfunction "+IN_5") (pintype "input"))
      (node (ref "IC4") (pin "6") (pinfunction "-IN_6") (pintype "input"))
      (node (ref "JP2") (pin "5") (pinfunction "5_5") (pintype "passive"))
      (node (ref "JP4") (pin "3") (pinfunction "3_3") (pintype "passive"))
      (node (ref "LED10") (pin "C") (pinfunction "C_C") (pintype "passive"))
      (node (ref "LED4") (pin "C") (pinfunction "C_C") (pintype "passive"))
      (node (ref "LED5") (pin "C") (pinfunction "C_C") (pintype "passive"))
      (node (ref "LED6") (pin "C") (pinfunction "C_C") (pintype "passive"))
      (node (ref "LED7") (pin "C") (pinfunction "C_C") (pintype "passive"))
      (node (ref "R1") (pin "1") (pinfunction "1_1") (pintype "passive"))
      (node (ref "R10") (pin "1") (pinfunction "1_1") (pintype "passive"))
      (node (ref "R16") (pin "1") (pinfunction "1_1") (pintype "passive"))
      (node (ref "R21") (pin "1") (pinfunction "1_1") (pintype "passive"))
      (node (ref "R22") (pin "1") (pinfunction "1_1") (pintype "passive"))
      (node (ref "R28") (pin "1") (pinfunction "1_1") (pintype "passive"))
      (node (ref "R50") (pin "2") (pinfunction "2_2") (pintype "passive"))
      (node (ref "R51") (pin "1") (pinfunction "1_1") (pintype "passive"))
      (node (ref "R8") (pin "1") (pinfunction "1_1") (pintype "passive"))
      (node (ref "RF_MIN") (pin "1") (pinfunction "1_1") (pintype "passive"))
      (node (ref "RJ_1") (pin "P$4") (pinfunction "P$4_P$4") (pintype "bidirectional"))
      (node (ref "RJ_2") (pin "P$4") (pinfunction "P$4_P$4") (pintype "bidirectional"))
      (node (ref "R_DELAY") (pin "1") (pinfunction "1_1") (pintype "passive"))
      (node (ref "R_ISEN_B") (pin "1") (pinfunction "1_1") (pintype "passive"))
      (node (ref "SV1") (pin "10") (pinfunction "10_10") (pintype "passive"))
      (node (ref "SV1") (pin "4") (pinfunction "4_4") (pintype "passive"))
      (node (ref "SV1") (pin "6") (pinfunction "6_6") (pintype "passive"))
      (node (ref "SV1") (pin "8") (pinfunction "8_8") (pintype "passive"))
      (node (ref "T2") (pin "2") (pinfunction "E_2") (pintype "passive"))
      (node (ref "T4") (pin "2") (pinfunction "E_2") (pintype "passive"))
      (node (ref "T5") (pin "2") (pinfunction "S_2") (pintype "passive"))
      (node (ref "T8") (pin "2") (pinfunction "E_2") (pintype "passive"))
      (node (ref "U$1") (pin "2") (pinfunction "VSS_2") (pintype "passive"))
      (node (ref "U$2") (pin "20") (pinfunction "AGND_20") (pintype "power_in"))
      (node (ref "U$2") (pin "5") (pinfunction "GND_5") (pintype "power_in"))
      (node (ref "U$3") (pin "10") (pinfunction "GND_10") (pintype "bidirectional"))
      (node (ref "U$3") (pin "8") (pinfunction "DIS_8") (pintype "bidirectional"))
      (node (ref "U$4") (pin "2") (pinfunction "GND_2") (pintype "bidirectional"))
      (node (ref "U$5") (pin "1") (pinfunction "NC_1") (pintype "bidirectional"))
      (node (ref "U$5") (pin "3") (pinfunction "CATHODE_3") (pintype "bidirectional"))
      (node (ref "U$5") (pin "4") (pinfunction "NC_4") (pintype "bidirectional"))
      (node (ref "U$6") (pin "1") (pinfunction "NC_1") (pintype "bidirectional"))
      (node (ref "U$6") (pin "4") (pinfunction "NC_4") (pintype "bidirectional"))
      (node (ref "U$8") (pin "3") (pinfunction "GND_3") (pintype "bidirectional"))
      (node (ref "U$8") (pin "5") (pinfunction "~{ON}/OFF_5") (pintype "bidirectional"))
      (node (ref "U1") (pin "11") (pinfunction "GND_11") (pintype "passive"))
      (node (ref "U2") (pin "4") (pinfunction "GND_4") (pintype "passive"))
      (node (ref "U3") (pin "6") (pinfunction "GND_6") (pintype "passive"))
      (node (ref "U4") (pin "6") (pinfunction "GND_6") (pintype "passive"))
      (node (ref "X1") (pin "2") (pinfunction "KL_2") (pintype "passive"))
    )
    (net (code "31") (name "GND1") (class "Default")
      (node (ref "C10") (pin "-") (pinfunction "-_-") (pintype "passive"))
      (node (ref "C13") (pin "2") (pinfunction "2_2") (pintype "passive"))
      (node (ref "C35") (pin "2") (pinfunction "2_2") (pintype "passive"))
      (node (ref "C50") (pin "2") (pinfunction "2_2") (pintype "passive"))
      (node (ref "C9") (pin "-") (pinfunction "-_-") (pintype "passive"))
      (node (ref "LED8") (pin "C") (pinfunction "C_C") (pintype "passive"))
      (node (ref "Q4") (pin "S") (pinfunction "S_S") (pintype "passive"))
      (node (ref "R54") (pin "2") (pinfunction "2_2") (pintype "passive"))
      (node (ref "T3") (pin "2") (pinfunction "E_2") (pintype "passive"))
      (node (ref "X2") (pin "1") (pinfunction "KL_1") (pintype "passive"))
    )
    (net (code "32") (name "INT_ETH") (class "Default")
      (node (ref "U$2") (pin "30") (pinfunction "PC0_30") (pintype "bidirectional"))
      (node (ref "U1") (pin "20") (pinfunction "B1_20") (pintype "bidirectional"))
    )
    (net (code "33") (name "INT_ETH_3V") (class "Default")
      (node (ref "JP1") (pin "5") (pinfunction "5_5") (pintype "passive"))
      (node (ref "U1") (pin "1") (pinfunction "A1_1") (pintype "bidirectional"))
    )
    (net (code "34") (name "KICK") (class "Default")
      (node (ref "R19") (pin "1") (pinfunction "1_1") (pintype "passive"))
      (node (ref "U$2") (pin "23") (pinfunction "PB3_23") (pintype "bidirectional"))
    )
    (net (code "35") (name "LINE") (class "Default")
      (node (ref "C48") (pin "1") (pinfunction "1_1") (pintype "passive"))
      (node (ref "D16") (pin "A") (pinfunction "A_A") (pintype "passive"))
      (node (ref "D17") (pin "A") (pinfunction "A_A") (pintype "passive"))
      (node (ref "R70") (pin "2") (pinfunction "2_2") (pintype "passive"))
      (node (ref "U$3") (pin "7") (pinfunction "LINE_7") (pintype "bidirectional"))
    )
    (net (code "36") (name "MISO") (class "Default")
      (node (ref "U$2") (pin "8") (pinfunction "PB0_8") (pintype "bidirectional"))
      (node (ref "U1") (pin "17") (pinfunction "B3_17") (pintype "bidirectional"))
    )
    (net (code "37") (name "MISO_3V") (class "Default")
      (node (ref "JP1") (pin "3") (pinfunction "3_3") (pintype "passive"))
      (node (ref "U1") (pin "4") (pinfunction "A3_4") (pintype "bidirectional"))
    )
    (net (code "38") (name "MOSI") (class "Default")
      (node (ref "U$2") (pin "9") (pinfunction "PB1_9") (pintype "bidirectional"))
      (node (ref "U1") (pin "16") (pinfunction "B4_16") (pintype "bidirectional"))
    )
    (net (code "39") (name "MOSI_3V") (class "Default")
      (node (ref "JP1") (pin "2") (pinfunction "2_2") (pintype "passive"))
      (node (ref "U1") (pin "5") (pinfunction "A4_5") (pintype "bidirectional"))
    )
    (net (code "40") (name "NOTAUS") (class "Default")
      (node (ref "D16") (pin "C") (pinfunction "C_C") (pintype "passive"))
      (node (ref "R14") (pin "1") (pinfunction "1_1") (pintype "passive"))
      (node (ref "R55") (pin "2") (pinfunction "2_2") (pintype "passive"))
      (node (ref "U2") (pin "7") (pinfunction "1Y_7") (pintype "output"))
    )
    (net (code "41") (name "Net-(COIL_IN-P)") (class "Default")
      (node (ref "COIL_IN") (pin "P$1") (pinfunction "P_P$1") (pintype "passive"))
      (node (ref "Q2") (pin "D") (pinfunction "D_D") (pintype "passive"))
      (node (ref "R20") (pin "2") (pinfunction "2_2") (pintype "passive"))
      (node (ref "U$7") (pin "A") (pinfunction "A_A") (pintype "passive"))
    )
    (net (code "42") (name "Net-(C_ISEN_A-Pad1)") (class "Default")
      (node (ref "C_ISEN_A") (pin "1") (pinfunction "1_1") (pintype "passive"))
      (node (ref "R_ISEN_A") (pin "2") (pinfunction "2_2") (pintype "passive"))
    )
    (net (code "43") (name "Net-(D3-PadA)") (class "Default")
      (node (ref "D3") (pin "A") (pinfunction "A_A") (pintype "passive"))
      (node (ref "D4") (pin "C") (pinfunction "C_C") (pintype "passive"))
      (node (ref "R_ISEN_A") (pin "1") (pinfunction "1_1") (pintype "passive"))
    )
    (net (code "44") (name "Net-(D5-C)") (class "Default")
      (node (ref "D5") (pin "K") (pinfunction "C_K") (pintype "passive"))
      (node (ref "R18") (pin "1") (pinfunction "1_1") (pintype "passive"))
      (node (ref "U$6") (pin "6") (pinfunction "VO_6") (pintype "bidirectional"))
      (node (ref "U$6") (pin "7") (pinfunction "VO_7") (pintype "bidirectional"))
    )
    (net (code "45") (name "Net-(D5-PadA)") (class "Default")
      (node (ref "D5") (pin "A") (pinfunction "A_A") (pintype "passive"))
      (node (ref "R13") (pin "1") (pinfunction "1_1") (pintype "passive"))
    )
    (net (code "46") (name "Net-(D6-C)") (class "Default")
      (node (ref "C19") (pin "2") (pinfunction "2_2") (pintype "passive"))
      (node (ref "D6") (pin "K") (pinfunction "C_K") (pintype "passive"))
      (node (ref "L5") (pin "2") (pinfunction "2_2") (pintype "passive"))
      (node (ref "U3") (pin "8") (pinfunction "VSW_8") (pintype "output"))
    )
    (net (code "47") (name "Net-(D7-C)") (class "Default")
      (node (ref "C22") (pin "2") (pinfunction "2_2") (pintype "passive"))
      (node (ref "D7") (pin "K") (pinfunction "C_K") (pintype "passive"))
      (node (ref "L6") (pin "2") (pinfunction "2_2") (pintype "passive"))
      (node (ref "U4") (pin "8") (pinfunction "VSW_8") (pintype "output"))
    )
    (net (code "48") (name "Net-(D10-C)") (class "Default")
      (node (ref "D10") (pin "K") (pinfunction "C_K") (pintype "passive"))
      (node (ref "D8") (pin "A") (pinfunction "A_A") (pintype "passive"))
      (node (ref "L7") (pin "2") (pinfunction "8_2") (pintype "passive"))
    )
    (net (code "49") (name "Net-(D11-C)") (class "Default")
      (node (ref "D11") (pin "K") (pinfunction "C_K") (pintype "passive"))
      (node (ref "D9") (pin "A") (pinfunction "A_A") (pintype "passive"))
      (node (ref "L7") (pin "4") (pinfunction "1_4") (pintype "passive"))
    )
    (net (code "50") (name "Net-(D15-C)") (class "Default")
      (node (ref "D15") (pin "K") (pinfunction "C_K") (pintype "passive"))
      (node (ref "L1") (pin "2") (pinfunction "2_2") (pintype "passive"))
      (node (ref "U$8") (pin "2") (pinfunction "VOUT_2") (pintype "bidirectional"))
    )
    (net (code "51") (name "Net-(IC1A-+IN)") (class "Default")
      (node (ref "C15") (pin "1") (pinfunction "1_1") (pintype "passive"))
      (node (ref "C32") (pin "1") (pinfunction "1_1") (pintype "passive"))
      (node (ref "IC1") (pin "3") (pinfunction "+IN_3") (pintype "input"))
      (node (ref "IC1") (pin "5") (pinfunction "+IN_5") (pintype "input"))
      (node (ref "R101") (pin "1") (pinfunction "1_1") (pintype "passive"))
      (node (ref "R6") (pin "2") (pinfunction "2_2") (pintype "passive"))
    )
    (net (code "52") (name "Net-(IC1A--IN)") (class "Default")
      (node (ref "C14") (pin "1") (pinfunction "1_1") (pintype "passive"))
      (node (ref "C51") (pin "1") (pinfunction "1_1") (pintype "passive"))
      (node (ref "IC1") (pin "2") (pinfunction "-IN_2") (pintype "input"))
      (node (ref "OK1") (pin "7") (pinfunction "EMIT_7") (pintype "passive"))
      (node (ref "R11") (pin "2") (pinfunction "2_2") (pintype "passive"))
    )
    (net (code "53") (name "Net-(IC1A-OUT)") (class "Default")
      (node (ref "IC1") (pin "1") (pinfunction "OUT_1") (pintype "output"))
      (node (ref "R105") (pin "1") (pinfunction "1_1") (pintype "passive"))
    )
    (net (code "54") (name "Net-(IC1B--IN)") (class "Default")
      (node (ref "C46") (pin "1") (pinfunction "1_1") (pintype "passive"))
      (node (ref "IC1") (pin "6") (pinfunction "-IN_6") (pintype "input"))
      (node (ref "R4") (pin "2") (pinfunction "2_2") (pintype "passive"))
      (node (ref "R7") (pin "1") (pinfunction "1_1") (pintype "passive"))
    )
    (net (code "55") (name "Net-(IC1B-OUT)") (class "Default")
      (node (ref "IC1") (pin "7") (pinfunction "OUT_7") (pintype "output"))
      (node (ref "R9") (pin "1") (pinfunction "1_1") (pintype "passive"))
    )
    (net (code "56") (name "Net-(IC2A-EN)") (class "Default")
      (node (ref "IC2") (pin "5") (pinfunction "EN_5") (pintype "input"))
      (node (ref "R58") (pin "1") (pinfunction "1_1") (pintype "passive"))
    )
    (net (code "57") (name "Net-(IC2A-Q2)") (class "Default")
      (node (ref "IC2") (pin "10") (pinfunction "Q2_10") (pintype "output"))
      (node (ref "U2") (pin "1") (pinfunction "1A_1") (pintype "input"))
    )
    (net (code "58") (name "Net-(IC2A-Q3)") (class "Default")
      (node (ref "IC2") (pin "1") (pinfunction "Q3_1") (pintype "output"))
      (node (ref "U2") (pin "2") (pinfunction "1B_2") (pintype "input"))
    )
    (net (code "59") (name "Net-(IC4A--IN)") (class "Default")
      (node (ref "C36") (pin "1") (pinfunction "1_1") (pintype "passive"))
      (node (ref "IC4") (pin "2") (pinfunction "-IN_2") (pintype "input"))
      (node (ref "R21") (pin "2") (pinfunction "2_2") (pintype "passive"))
      (node (ref "R5") (pin "1") (pinfunction "1_1") (pintype "passive"))
      (node (ref "R52") (pin "2") (pinfunction "2_2") (pintype "passive"))
    )
    (net (code "60") (name "Net-(IC4A-OUT)") (class "Default")
      (node (ref "IC4") (pin "1") (pinfunction "OUT_1") (pintype "output"))
      (node (ref "U2") (pin "6") (pinfunction "2B_6") (pintype "input"))
    )
    (net (code "61") (name "Net-(L7-4)") (class "Default")
      (node (ref "L3") (pin "1") (pinfunction "1_1") (pintype "passive"))
      (node (ref "L4") (pin "1") (pinfunction "1_1") (pintype "passive"))
      (node (ref "L7") (pin "9") (pinfunction "4_9") (pintype "passive"))
    )
    (net (code "62") (name "Net-(L7-5)") (class "Default")
      (node (ref "C13") (pin "1") (pinfunction "1_1") (pintype "passive"))
      (node (ref "C_ISEN_A") (pin "2") (pinfunction "2_2") (pintype "passive"))
      (node (ref "L3") (pin "2") (pinfunction "2_2") (pintype "passive"))
      (node (ref "L7") (pin "11") (pinfunction "5_11") (pintype "passive"))
    )
    (net (code "63") (name "Net-(LED1-PadA)") (class "Default")
      (node (ref "LED1") (pin "A") (pinfunction "A_A") (pintype "passive"))
      (node (ref "R39") (pin "1") (pinfunction "1_1") (pintype "passive"))
    )
    (net (code "64") (name "Net-(LED2-PadA)") (class "Default")
      (node (ref "LED2") (pin "A") (pinfunction "A_A") (pintype "passive"))
      (node (ref "R40") (pin "1") (pinfunction "1_1") (pintype "passive"))
    )
    (net (code "65") (name "Net-(LED3-PadA)") (class "Default")
      (node (ref "LED3") (pin "A") (pinfunction "A_A") (pintype "passive"))
      (node (ref "R41") (pin "1") (pinfunction "1_1") (pintype "passive"))
    )
    (net (code "66") (name "Net-(LED4-PadA)") (class "Default")
      (node (ref "LED4") (pin "A") (pinfunction "A_A") (pintype "passive"))
      (node (ref "R42") (pin "1") (pinfunction "1_1") (pintype "passive"))
    )
    (net (code "67") (name "Net-(LED5-PadA)") (class "Default")
      (node (ref "LED5") (pin "A") (pinfunction "A_A") (pintype "passive"))
      (node (ref "R43") (pin "1") (pinfunction "1_1") (pintype "passive"))
    )
    (net (code "68") (name "Net-(LED6-PadA)") (class "Default")
      (node (ref "LED6") (pin "A") (pinfunction "A_A") (pintype "passive"))
      (node (ref "R44") (pin "1") (pinfunction "1_1") (pintype "passive"))
    )
    (net (code "69") (name "Net-(LED7-PadA)") (class "Default")
      (node (ref "LED7") (pin "A") (pinfunction "A_A") (pintype "passive"))
      (node (ref "R45") (pin "1") (pinfunction "1_1") (pintype "passive"))
    )
    (net (code "70") (name "Net-(LED8-PadA)") (class "Default")
      (node (ref "LED8") (pin "A") (pinfunction "A_A") (pintype "passive"))
      (node (ref "R46") (pin "1") (pinfunction "1_1") (pintype "passive"))
    )
    (net (code "71") (name "Net-(LED9-PadA)") (class "Default")
      (node (ref "LED9") (pin "A") (pinfunction "A_A") (pintype "passive"))
      (node (ref "R49") (pin "1") (pinfunction "1_1") (pintype "passive"))
    )
    (net (code "72") (name "Net-(LED10-PadA)") (class "Default")
      (node (ref "LED10") (pin "A") (pinfunction "A_A") (pintype "passive"))
      (node (ref "R59") (pin "1") (pinfunction "1_1") (pintype "passive"))
    )
    (net (code "73") (name "Net-(OK1A-A)") (class "Default")
      (node (ref "OK1") (pin "1") (pinfunction "A_1") (pintype "passive"))
      (node (ref "R105") (pin "2") (pinfunction "2_2") (pintype "passive"))
    )
    (net (code "74") (name "Net-(OK1A-C)") (class "Default")
      (node (ref "OK1") (pin "2") (pinfunction "C_2") (pintype "passive"))
      (node (ref "OK1") (pin "3") (pinfunction "A_3") (pintype "passive"))
    )
    (net (code "75") (name "Net-(OK2A-A)") (class "Default")
      (node (ref "OK2") (pin "1") (pinfunction "A_1") (pintype "passive"))
      (node (ref "R9") (pin "2") (pinfunction "2_2") (pintype "passive"))
    )
    (net (code "76") (name "Net-(Q2-PadG)") (class "Default")
      (node (ref "Q2") (pin "G") (pinfunction "G_G") (pintype "passive"))
      (node (ref "R13") (pin "2") (pinfunction "2_2") (pintype "passive"))
      (node (ref "R18") (pin "2") (pinfunction "2_2") (pintype "passive"))
    )
    (net (code "77") (name "Net-(Q5-G)") (class "Default")
      (node (ref "D13") (pin "C") (pinfunction "C_C") (pintype "passive"))
      (node (ref "Q5") (pin "1") (pinfunction "G_1") (pintype "passive"))
      (node (ref "R200") (pin "1") (pinfunction "1_1") (pintype "passive"))
    )
    (net (code "78") (name "Net-(Q6-PadD)") (class "Default")
      (node (ref "Q6") (pin "D") (pinfunction "D_D") (pintype "passive"))
      (node (ref "R3") (pin "2") (pinfunction "2_2") (pintype "passive"))
    )
    (net (code "79") (name "Net-(Q6-PadG)") (class "Default")
      (node (ref "Q6") (pin "G") (pinfunction "G_G") (pintype "passive"))
      (node (ref "R12") (pin "2") (pinfunction "2_2") (pintype "passive"))
      (node (ref "T6") (pin "C") (pinfunction "C_C") (pintype "passive"))
    )
    (net (code "80") (name "Net-(R2-Pad2)") (class "Default")
      (node (ref "R2") (pin "2") (pinfunction "2_2") (pintype "passive"))
      (node (ref "R3") (pin "1") (pinfunction "1_1") (pintype "passive"))
    )
    (net (code "81") (name "Net-(R15-Pad1)") (class "Default")
      (node (ref "R15") (pin "1") (pinfunction "1_1") (pintype "passive"))
      (node (ref "U$5") (pin "6") (pinfunction "VO_6") (pintype "bidirectional"))
      (node (ref "U$5") (pin "7") (pinfunction "VO_7") (pintype "bidirectional"))
    )
    (net (code "82") (name "Net-(R15-Pad2)") (class "Default")
      (node (ref "R15") (pin "2") (pinfunction "2_2") (pintype "passive"))
      (node (ref "T6") (pin "B") (pinfunction "B_B") (pintype "passive"))
    )
    (net (code "83") (name "Net-(R32-Pad1)") (class "Default")
      (node (ref "R32") (pin "1") (pinfunction "1_1") (pintype "passive"))
      (node (ref "SJ1") (pin "1") (pinfunction "1_1") (pintype "passive"))
    )
    (net (code "84") (name "Net-(T2-B)") (class "Default")
      (node (ref "R19") (pin "2") (pinfunction "2_2") (pintype "passive"))
      (node (ref "R51") (pin "2") (pinfunction "2_2") (pintype "passive"))
      (node (ref "T2") (pin "1") (pinfunction "B_1") (pintype "passive"))
    )
    (net (code "85") (name "Net-(T2-C)") (class "Default")
      (node (ref "D17") (pin "C") (pinfunction "C_C") (pintype "passive"))
      (node (ref "T2") (pin "3") (pinfunction "C_3") (pintype "passive"))
      (node (ref "U$6") (pin "3") (pinfunction "CATHODE_3") (pintype "bidirectional"))
    )
    (net (code "86") (name "Net-(T3-B)") (class "Default")
      (node (ref "R24") (pin "2") (pinfunction "2_2") (pintype "passive"))
      (node (ref "T3") (pin "1") (pinfunction "B_1") (pintype "passive"))
    )
    (net (code "87") (name "Net-(T3-C)") (class "Default")
      (node (ref "D13") (pin "A") (pinfunction "A_A") (pintype "passive"))
      (node (ref "T3") (pin "3") (pinfunction "C_3") (pintype "passive"))
    )
    (net (code "88") (name "Net-(T4-B)") (class "Default")
      (node (ref "R25") (pin "2") (pinfunction "2_2") (pintype "passive"))
      (node (ref "T4") (pin "1") (pinfunction "B_1") (pintype "passive"))
    )
    (net (code "89") (name "Net-(T4-C)") (class "Default")
      (node (ref "R26") (pin "1") (pinfunction "1_1") (pintype "passive"))
      (node (ref "T4") (pin "3") (pinfunction "C_3") (pintype "passive"))
      (node (ref "U2") (pin "5") (pinfunction "2A_5") (pintype "input"))
    )
    (net (code "90") (name "Net-(T5-D)") (class "Default")
      (node (ref "JP3") (pin "3") (pinfunction "3_3") (pintype "passive"))
      (node (ref "T5") (pin "1") (pinfunction "D_1") (pintype "passive"))
    )
    (net (code "91") (name "Net-(T5-G)") (class "Default")
      (node (ref "R16") (pin "2") (pinfunction "2_2") (pintype "passive"))
      (node (ref "R47") (pin "2") (pinfunction "2_2") (pintype "passive"))
      (node (ref "T5") (pin "3") (pinfunction "G_3") (pintype "passive"))
    )
    (net (code "92") (name "Net-(T8-B)") (class "Default")
      (node (ref "C49") (pin "1") (pinfunction "1_1") (pintype "passive"))
      (node (ref "R48") (pin "2") (pinfunction "2_2") (pintype "passive"))
      (node (ref "T8") (pin "1") (pinfunction "B_1") (pintype "passive"))
    )
    (net (code "93") (name "Net-(T8-C)") (class "Default")
      (node (ref "RF_MAX") (pin "1") (pinfunction "1_1") (pintype "passive"))
      (node (ref "T8") (pin "3") (pinfunction "C_3") (pintype "passive"))
    )
    (net (code "94") (name "Net-(U$1-RS)") (class "Default")
      (node (ref "R1") (pin "2") (pinfunction "2_2") (pintype "passive"))
      (node (ref "U$1") (pin "8") (pinfunction "RS_8") (pintype "input"))
    )
    (net (code "95") (name "Net-(U$2-AREF)") (class "Default")
      (node (ref "C6") (pin "2") (pinfunction "2_2") (pintype "passive"))
      (node (ref "U$2") (pin "21") (pinfunction "AREF_21") (pintype "bidirectional"))
    )
    (net (code "96") (name "Net-(U$2-PC4)") (class "Default")
      (node (ref "R57") (pin "1") (pinfunction "1_1") (pintype "passive"))
      (node (ref "U$2") (pin "17") (pinfunction "PC4_17") (pintype "bidirectional"))
    )
    (net (code "97") (name "Net-(U$2-PC6)") (class "Default")
      (node (ref "R55") (pin "1") (pinfunction "1_1") (pintype "passive"))
      (node (ref "U$2") (pin "22") (pinfunction "PC6_22") (pintype "bidirectional"))
    )
    (net (code "98") (name "Net-(U$2-PE1(XTAL1))") (class "Default")
      (node (ref "C5") (pin "2") (pinfunction "2_2") (pintype "passive"))
      (node (ref "Q1") (pin "1") (pinfunction "1_1") (pintype "passive"))
      (node (ref "U$2") (pin "10") (pinfunction "PE1(XTAL1)_10") (pintype "bidirectional"))
    )
    (net (code "99") (name "Net-(U$2-PE2(XTAL2))") (class "Default")
      (node (ref "C4") (pin "2") (pinfunction "2_2") (pintype "passive"))
      (node (ref "Q1") (pin "2") (pinfunction "2_2") (pintype "passive"))
      (node (ref "U$2") (pin "11") (pinfunction "PE2(XTAL2)_11") (pintype "bidirectional"))
    )
    (net (code "100") (name "Net-(U$3-CF)") (class "Default")
      (node (ref "CF") (pin "1") (pinfunction "1_1") (pintype "passive"))
      (node (ref "U$3") (pin "3") (pinfunction "CF_3") (pintype "bidirectional"))
    )
    (net (code "101") (name "Net-(U$3-CSS)") (class "Default")
      (node (ref "CSS") (pin "1") (pinfunction "1_1") (pintype "passive"))
      (node (ref "R_SS") (pin "1") (pinfunction "1_1") (pintype "passive"))
      (node (ref "U$3") (pin "1") (pinfunction "CSS_1") (pintype "bidirectional"))
    )
    (net (code "102") (name "Net-(U$3-DELAY)") (class "Default")
      (node (ref "C_DELAY") (pin "1") (pinfunction "1_1") (pintype "passive"))
      (node (ref "R_DELAY") (pin "2") (pinfunction "2_2") (pintype "passive"))
      (node (ref "U$3") (pin "2") (pinfunction "DELAY_2") (pintype "bidirectional"))
    )
    (net (code "103") (name "Net-(U$3-HVG)") (class "Default")
      (node (ref "Q3") (pin "G") (pinfunction "G_G") (pintype "passive"))
      (node (ref "R53") (pin "1") (pinfunction "1_1") (pintype "passive"))
      (node (ref "U$3") (pin "15") (pinfunction "HVG_15") (pintype "bidirectional"))
    )
    (net (code "104") (name "Net-(U$3-ISEN)") (class "Default")
      (node (ref "C_ISEN_B") (pin "1") (pinfunction "1_1") (pintype "passive"))
      (node (ref "D3") (pin "C") (pinfunction "C_C") (pintype "passive"))
      (node (ref "R_ISEN_B") (pin "2") (pinfunction "2_2") (pintype "passive"))
      (node (ref "U$3") (pin "6") (pinfunction "ISEN_6") (pintype "bidirectional"))
    )
    (net (code "105") (name "Net-(U$3-LVG)") (class "Default")
      (node (ref "Q4") (pin "G") (pinfunction "G_G") (pintype "passive"))
      (node (ref "R54") (pin "1") (pinfunction "1_1") (pintype "passive"))
      (node (ref "U$3") (pin "11") (pinfunction "LVG_11") (pintype "bidirectional"))
    )
    (net (code "106") (name "Net-(U$3-OUT)") (class "Default")
      (node (ref "C_BOOT") (pin "2") (pinfunction "2_2") (pintype "passive"))
      (node (ref "L4") (pin "2") (pinfunction "2_2") (pintype "passive"))
      (node (ref "Q3") (pin "S") (pinfunction "S_S") (pintype "passive"))
      (node (ref "Q4") (pin "D") (pinfunction "D_D") (pintype "passive"))
      (node (ref "R53") (pin "2") (pinfunction "2_2") (pintype "passive"))
      (node (ref "U$3") (pin "14") (pinfunction "OUT_14") (pintype "bidirectional"))
    )
    (net (code "107") (name "Net-(U$3-RFMIN)") (class "Default")
      (node (ref "RF_MAX") (pin "2") (pinfunction "2_2") (pintype "passive"))
      (node (ref "RF_MIN") (pin "2") (pinfunction "2_2") (pintype "passive"))
      (node (ref "R_SS") (pin "2") (pinfunction "2_2") (pintype "passive"))
      (node (ref "U$3") (pin "4") (pinfunction "RFMIN_4") (pintype "bidirectional"))
    )
    (net (code "108") (name "Net-(U$3-VBOOT)") (class "Default")
      (node (ref "C_BOOT") (pin "1") (pinfunction "1_1") (pintype "passive"))
      (node (ref "U$3") (pin "16") (pinfunction "VBOOT_16") (pintype "bidirectional"))
    )
    (net (code "109") (name "Net-(U$5-ANODE)") (class "Default")
      (node (ref "R14") (pin "2") (pinfunction "2_2") (pintype "passive"))
      (node (ref "U$5") (pin "2") (pinfunction "ANODE_2") (pintype "bidirectional"))
    )
    (net (code "110") (name "Net-(U$6-ANODE)") (class "Default")
      (node (ref "R17") (pin "1") (pinfunction "1_1") (pintype "passive"))
      (node (ref "U$6") (pin "2") (pinfunction "ANODE_2") (pintype "bidirectional"))
    )
    (net (code "111") (name "Net-(U3-CB)") (class "Default")
      (node (ref "C19") (pin "1") (pinfunction "1_1") (pintype "passive"))
      (node (ref "U3") (pin "1") (pinfunction "CB_1") (pintype "input"))
    )
    (net (code "112") (name "Net-(U4-CB)") (class "Default")
      (node (ref "C22") (pin "1") (pinfunction "1_1") (pintype "passive"))
      (node (ref "U4") (pin "1") (pinfunction "CB_1") (pintype "input"))
    )
    (net (code "113") (name "Net-(VR1-C)") (class "Default")
      (node (ref "LED1") (pin "C") (pinfunction "C_C") (pintype "passive"))
      (node (ref "VR1") (pin "1") (pinfunction "C_1") (pintype "passive"))
    )
    (net (code "114") (name "Net-(VR1-R)") (class "Default")
      (node (ref "R33") (pin "1") (pinfunction "1_1") (pintype "passive"))
      (node (ref "R36") (pin "2") (pinfunction "2_2") (pintype "passive"))
      (node (ref "VR1") (pin "2") (pinfunction "R_2") (pintype "passive"))
    )
    (net (code "115") (name "Net-(VR2-C)") (class "Default")
      (node (ref "LED2") (pin "C") (pinfunction "C_C") (pintype "passive"))
      (node (ref "VR2") (pin "1") (pinfunction "C_1") (pintype "passive"))
    )
    (net (code "116") (name "Net-(VR2-R)") (class "Default")
      (node (ref "R34") (pin "1") (pinfunction "1_1") (pintype "passive"))
      (node (ref "R37") (pin "2") (pinfunction "2_2") (pintype "passive"))
      (node (ref "VR2") (pin "2") (pinfunction "R_2") (pintype "passive"))
    )
    (net (code "117") (name "Net-(VR3-C)") (class "Default")
      (node (ref "LED3") (pin "C") (pinfunction "C_C") (pintype "passive"))
      (node (ref "VR3") (pin "1") (pinfunction "C_1") (pintype "passive"))
    )
    (net (code "118") (name "Net-(VR3-R)") (class "Default")
      (node (ref "R35") (pin "1") (pinfunction "1_1") (pintype "passive"))
      (node (ref "R38") (pin "2") (pinfunction "2_2") (pintype "passive"))
      (node (ref "VR3") (pin "2") (pinfunction "R_2") (pintype "passive"))
    )
    (net (code "119") (name "Net-(X1A-KL)") (class "Default")
      (node (ref "F1") (pin "2") (pinfunction "2_2") (pintype "passive"))
      (node (ref "R59") (pin "2") (pinfunction "2_2") (pintype "passive"))
      (node (ref "X1") (pin "1") (pinfunction "KL_1") (pintype "passive"))
    )
    (net (code "120") (name "OC0A{slash}MOSI_A") (class "Default")
      (node (ref "JP4") (pin "1") (pinfunction "1_1") (pintype "passive"))
      (node (ref "SV1") (pin "1") (pinfunction "1_1") (pintype "passive"))
      (node (ref "U$2") (pin "2") (pinfunction "(MOSI_A/TXD)PD3_2") (pintype "bidirectional"))
    )
    (net (code "121") (name "OC1A_FREQ{slash}MISO_A") (class "Default")
      (node (ref "R48") (pin "1") (pinfunction "1_1") (pintype "passive"))
      (node (ref "SV1") (pin "9") (pinfunction "9_9") (pintype "passive"))
      (node (ref "U$2") (pin "1") (pinfunction "(MISO_A)PD2_1") (pintype "bidirectional"))
    )
    (net (code "122") (name "RESET_NOTAUS") (class "Default")
      (node (ref "IC2") (pin "11") (pinfunction "R2_11") (pintype "input"))
      (node (ref "IC2") (pin "15") (pinfunction "R3_15") (pintype "input"))
      (node (ref "U$2") (pin "24") (pinfunction "PB4_24") (pintype "bidirectional"))
    )
    (net (code "123") (name "RST") (class "Default")
      (node (ref "SV1") (pin "5") (pinfunction "5_5") (pintype "passive"))
      (node (ref "U$2") (pin "31") (pinfunction "PE0(RESET)_31") (pintype "input"))
    )
    (net (code "124") (name "RST_ETH") (class "Default")
      (node (ref "U$2") (pin "32") (pinfunction "PD1_32") (pintype "bidirectional"))
      (node (ref "U1") (pin "14") (pinfunction "B6_14") (pintype "bidirectional"))
    )
    (net (code "125") (name "RST_ETH_3V") (class "Default")
      (node (ref "JP2") (pin "3") (pinfunction "3_3") (pintype "passive"))
      (node (ref "U1") (pin "7") (pinfunction "A6_7") (pintype "bidirectional"))
    )
    (net (code "126") (name "SCK") (class "Default")
      (node (ref "U$2") (pin "28") (pinfunction "(SCK)PB7_28") (pintype "bidirectional"))
      (node (ref "U1") (pin "15") (pinfunction "B5_15") (pintype "bidirectional"))
    )
    (net (code "127") (name "SCK_3V") (class "Default")
      (node (ref "JP1") (pin "1") (pinfunction "1_1") (pintype "passive"))
      (node (ref "U1") (pin "6") (pinfunction "A5_6") (pintype "bidirectional"))
    )
    (net (code "128") (name "SERVO_PWM") (class "Default")
      (node (ref "JP3") (pin "1") (pinfunction "1_1") (pintype "passive"))
      (node (ref "U$2") (pin "3") (pinfunction "PC1_3") (pintype "bidirectional"))
    )
    (net (code "129") (name "STBY") (class "Default")
      (node (ref "C12") (pin "1") (pinfunction "1_1") (pintype "passive"))
      (node (ref "R57") (pin "2") (pinfunction "2_2") (pintype "passive"))
      (node (ref "U$3") (pin "5") (pinfunction "STBY_5") (pintype "bidirectional"))
      (node (ref "U2") (pin "3") (pinfunction "2Y_3") (pintype "output"))
    )
    (net (code "130") (name "TASTER") (class "Default")
      (node (ref "C33") (pin "1") (pinfunction "1_1") (pintype "passive"))
      (node (ref "IC2") (pin "14") (pinfunction "S3_14") (pintype "input"))
      (node (ref "R22") (pin "2") (pinfunction "2_2") (pintype "passive"))
      (node (ref "S1") (pin "3") (pinfunction "P_3") (pintype "passive"))
      (node (ref "S1") (pin "4") (pinfunction "P1_4") (pintype "passive"))
    )
    (net (code "131") (name "WOL_ETH") (class "Default")
      (node (ref "U1") (pin "18") (pinfunction "B2_18") (pintype "bidirectional"))
    )
    (net (code "132") (name "WOL_ETH_3V") (class "Default")
      (node (ref "JP1") (pin "4") (pinfunction "4_4") (pintype "passive"))
      (node (ref "U1") (pin "3") (pinfunction "A2_3") (pintype "bidirectional"))
    )
    (net (code "133") (name "unconnected-(IC2A-Q0-Pad2)") (class "Default")
      (node (ref "IC2") (pin "2") (pinfunction "Q0_2") (pintype "output"))
    )
    (net (code "134") (name "unconnected-(IC2A-Q1-Pad9)") (class "Default")
      (node (ref "IC2") (pin "9") (pinfunction "Q1_9") (pintype "output"))
    )
    (net (code "135") (name "unconnected-(IC4B-OUT-Pad7)") (class "Default")
      (node (ref "IC4") (pin "7") (pinfunction "OUT_7") (pintype "output"))
    )
    (net (code "136") (name "unconnected-(L7-2-Pad8)") (class "Default")
      (node (ref "L7") (pin "8") (pinfunction "2_8") (pintype "passive"))
    )
    (net (code "137") (name "unconnected-(L7-3-Pad10)") (class "Default")
      (node (ref "L7") (pin "10") (pinfunction "3_10") (pintype "passive"))
    )
    (net (code "138") (name "unconnected-(L7-7-Pad5)") (class "Default")
      (node (ref "L7") (pin "5") (pinfunction "7_5") (pintype "passive"))
    )
    (net (code "139") (name "unconnected-(L7-Pad6)") (class "Default")
      (node (ref "L7") (pin "6") (pinfunction "6_6") (pintype "passive"))
    )
    (net (code "140") (name "unconnected-(OK2B-A-Pad3)") (class "Default")
      (node (ref "OK2") (pin "3") (pinfunction "A_3") (pintype "passive"))
    )
    (net (code "141") (name "unconnected-(OK2B-C-Pad4)") (class "Default")
      (node (ref "OK2") (pin "4") (pinfunction "C_4") (pintype "passive"))
    )
    (net (code "142") (name "unconnected-(OK2B-COL-Pad6)") (class "Default")
      (node (ref "OK2") (pin "6") (pinfunction "COL_6") (pintype "passive"))
    )
    (net (code "143") (name "unconnected-(OK2B-EMIT-Pad5)") (class "Default")
      (node (ref "OK2") (pin "5") (pinfunction "EMIT_5") (pintype "passive"))
    )
    (net (code "144") (name "unconnected-(RJ_1-PadP$1)") (class "Default")
      (node (ref "RJ_1") (pin "P$1") (pinfunction "P$1_P$1") (pintype "bidirectional"))
    )
    (net (code "145") (name "unconnected-(RJ_2-PadP$1)") (class "Default")
      (node (ref "RJ_2") (pin "P$1") (pinfunction "P$1_P$1") (pintype "bidirectional"))
    )
    (net (code "146") (name "unconnected-(SV1-Pad3)") (class "Default")
      (node (ref "SV1") (pin "3") (pinfunction "3_3") (pintype "passive"))
    )
    (net (code "147") (name "unconnected-(U$1-VREF-Pad5)") (class "Default")
      (node (ref "U$1") (pin "5") (pinfunction "VREF_5") (pintype "output"))
    )
    (net (code "148") (name "unconnected-(U$3-NC-Pad13)") (class "Default")
      (node (ref "U$3") (pin "13") (pinfunction "NC_13") (pintype "bidirectional"))
    )
    (net (code "149") (name "unconnected-(U$3-PFC_STOP-Pad9)") (class "Default")
      (node (ref "U$3") (pin "9") (pinfunction "PFC_STOP_9") (pintype "bidirectional"))
    )
    (net (code "150") (name "unconnected-(U$4-0V-Pad5)") (class "Default")
      (node (ref "U$4") (pin "5") (pinfunction "0V_5") (pintype "bidirectional"))
    )
    (net (code "151") (name "unconnected-(U3-NC-Pad3)") (class "Default")
      (node (ref "U3") (pin "3") (pinfunction "NC_3") (pintype "no_connect"))
    )
    (net (code "152") (name "unconnected-(U3-NC_2-Pad2)") (class "Default")
      (node (ref "U3") (pin "2") (pinfunction "NC_2_2") (pintype "no_connect"))
    )
    (net (code "153") (name "unconnected-(U3-ON{slash}~{OFF}-Pad5)") (class "Default")
      (node (ref "U3") (pin "5") (pinfunction "ON/~{OFF}_5") (pintype "input"))
    )
    (net (code "154") (name "unconnected-(U4-NC-Pad3)") (class "Default")
      (node (ref "U4") (pin "3") (pinfunction "NC_3") (pintype "no_connect"))
    )
    (net (code "155") (name "unconnected-(U4-NC_2-Pad2)") (class "Default")
      (node (ref "U4") (pin "2") (pinfunction "NC_2_2") (pintype "no_connect"))
    )
    (net (code "156") (name "unconnected-(U4-ON{slash}~{OFF}-Pad5)") (class "Default")
      (node (ref "U4") (pin "5") (pinfunction "ON/~{OFF}_5") (pintype "input"))
    )
    (net (code "157") (name "ÜBERSPANNUNG") (class "Default")
      (node (ref "C24") (pin "1") (pinfunction "1_1") (pintype "passive"))
      (node (ref "C41") (pin "1") (pinfunction "1_1") (pintype "passive"))
      (node (ref "IC2") (pin "12") (pinfunction "S2_12") (pintype "input"))
      (node (ref "OK2") (pin "7") (pinfunction "EMIT_7") (pintype "passive"))
      (node (ref "R10") (pin "2") (pinfunction "2_2") (pintype "passive"))
    )
  )
)
